# RGB_Matrix.net
KiCad netlist of a schematic drawn in Altium Designer
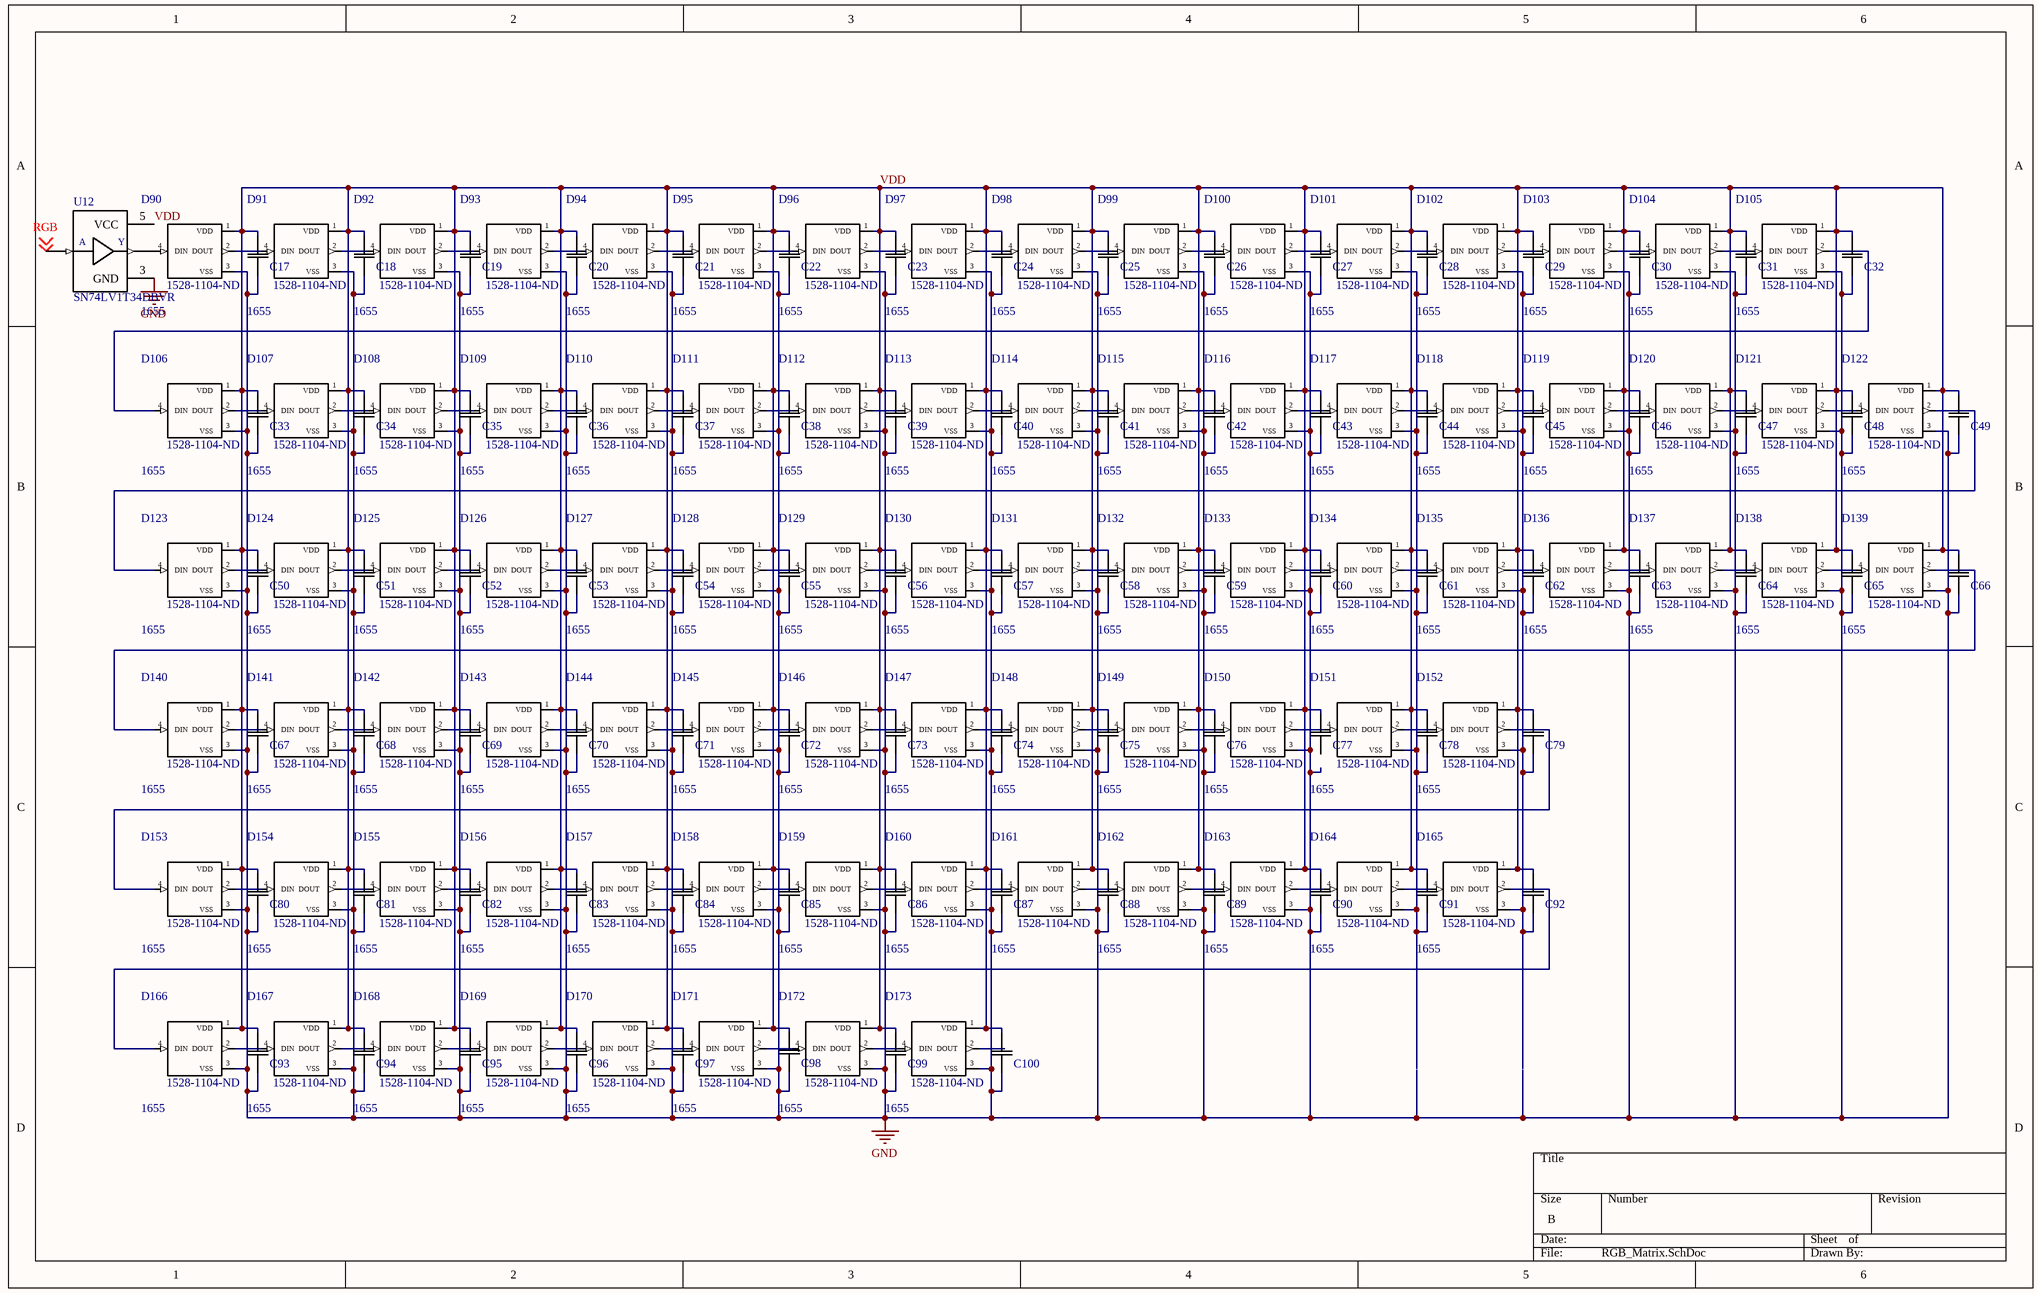
[diagram p0: RGB_Matrix.SchDoc]

(export (version "E")
  (design (tool "Eeschema 10.0.6"))
  (components
    (comp (ref "C17")
      (value "Part Number: RCER71H104K0DBH03A")
      (footprint "RCER71H104K0DBH0")
      (description "No Description Available")
      (fields
        (field (name "MANUFACTURER_PART_NUMBER") "RCER71H104K0DBH03A")
        (field (name "COPYRIGHT") "Copyright (C) 2015 Accelerated Designs. All rights reserved")
      )
      (libsource (lib "RCER71H104K0DBH03A") (part "RCER71H104K0DBH0"))
    )
    (comp (ref "C18")
      (value "Part Number: RCER71H104K0DBH03A")
      (footprint "RCER71H104K0DBH0")
      (description "No Description Available")
      (fields
        (field (name "MANUFACTURER_PART_NUMBER") "RCER71H104K0DBH03A")
        (field (name "COPYRIGHT") "Copyright (C) 2015 Accelerated Designs. All rights reserved")
      )
      (libsource (lib "RCER71H104K0DBH03A") (part "RCER71H104K0DBH0"))
    )
    (comp (ref "C19")
      (value "Part Number: RCER71H104K0DBH03A")
      (footprint "RCER71H104K0DBH0")
      (description "No Description Available")
      (fields
        (field (name "MANUFACTURER_PART_NUMBER") "RCER71H104K0DBH03A")
        (field (name "COPYRIGHT") "Copyright (C) 2015 Accelerated Designs. All rights reserved")
      )
      (libsource (lib "RCER71H104K0DBH03A") (part "RCER71H104K0DBH0"))
    )
    (comp (ref "C20")
      (value "Part Number: RCER71H104K0DBH03A")
      (footprint "RCER71H104K0DBH0")
      (description "No Description Available")
      (fields
        (field (name "MANUFACTURER_PART_NUMBER") "RCER71H104K0DBH03A")
        (field (name "COPYRIGHT") "Copyright (C) 2015 Accelerated Designs. All rights reserved")
      )
      (libsource (lib "RCER71H104K0DBH03A") (part "RCER71H104K0DBH0"))
    )
    (comp (ref "C21")
      (value "Part Number: RCER71H104K0DBH03A")
      (footprint "RCER71H104K0DBH0")
      (description "No Description Available")
      (fields
        (field (name "MANUFACTURER_PART_NUMBER") "RCER71H104K0DBH03A")
        (field (name "COPYRIGHT") "Copyright (C) 2015 Accelerated Designs. All rights reserved")
      )
      (libsource (lib "RCER71H104K0DBH03A") (part "RCER71H104K0DBH0"))
    )
    (comp (ref "C22")
      (value "Part Number: RCER71H104K0DBH03A")
      (footprint "RCER71H104K0DBH0")
      (description "No Description Available")
      (fields
        (field (name "MANUFACTURER_PART_NUMBER") "RCER71H104K0DBH03A")
        (field (name "COPYRIGHT") "Copyright (C) 2015 Accelerated Designs. All rights reserved")
      )
      (libsource (lib "RCER71H104K0DBH03A") (part "RCER71H104K0DBH0"))
    )
    (comp (ref "C23")
      (value "Part Number: RCER71H104K0DBH03A")
      (footprint "RCER71H104K0DBH0")
      (description "No Description Available")
      (fields
        (field (name "MANUFACTURER_PART_NUMBER") "RCER71H104K0DBH03A")
        (field (name "COPYRIGHT") "Copyright (C) 2015 Accelerated Designs. All rights reserved")
      )
      (libsource (lib "RCER71H104K0DBH03A") (part "RCER71H104K0DBH0"))
    )
    (comp (ref "C24")
      (value "Part Number: RCER71H104K0DBH03A")
      (footprint "RCER71H104K0DBH0")
      (description "No Description Available")
      (fields
        (field (name "MANUFACTURER_PART_NUMBER") "RCER71H104K0DBH03A")
        (field (name "COPYRIGHT") "Copyright (C) 2015 Accelerated Designs. All rights reserved")
      )
      (libsource (lib "RCER71H104K0DBH03A") (part "RCER71H104K0DBH0"))
    )
    (comp (ref "C25")
      (value "Part Number: RCER71H104K0DBH03A")
      (footprint "RCER71H104K0DBH0")
      (description "No Description Available")
      (fields
        (field (name "MANUFACTURER_PART_NUMBER") "RCER71H104K0DBH03A")
        (field (name "COPYRIGHT") "Copyright (C) 2015 Accelerated Designs. All rights reserved")
      )
      (libsource (lib "RCER71H104K0DBH03A") (part "RCER71H104K0DBH0"))
    )
    (comp (ref "C26")
      (value "Part Number: RCER71H104K0DBH03A")
      (footprint "RCER71H104K0DBH0")
      (description "No Description Available")
      (fields
        (field (name "MANUFACTURER_PART_NUMBER") "RCER71H104K0DBH03A")
        (field (name "COPYRIGHT") "Copyright (C) 2015 Accelerated Designs. All rights reserved")
      )
      (libsource (lib "RCER71H104K0DBH03A") (part "RCER71H104K0DBH0"))
    )
    (comp (ref "C27")
      (value "Part Number: RCER71H104K0DBH03A")
      (footprint "RCER71H104K0DBH0")
      (description "No Description Available")
      (fields
        (field (name "MANUFACTURER_PART_NUMBER") "RCER71H104K0DBH03A")
        (field (name "COPYRIGHT") "Copyright (C) 2015 Accelerated Designs. All rights reserved")
      )
      (libsource (lib "RCER71H104K0DBH03A") (part "RCER71H104K0DBH0"))
    )
    (comp (ref "C28")
      (value "Part Number: RCER71H104K0DBH03A")
      (footprint "RCER71H104K0DBH0")
      (description "No Description Available")
      (fields
        (field (name "MANUFACTURER_PART_NUMBER") "RCER71H104K0DBH03A")
        (field (name "COPYRIGHT") "Copyright (C) 2015 Accelerated Designs. All rights reserved")
      )
      (libsource (lib "RCER71H104K0DBH03A") (part "RCER71H104K0DBH0"))
    )
    (comp (ref "C29")
      (value "Part Number: RCER71H104K0DBH03A")
      (footprint "RCER71H104K0DBH0")
      (description "No Description Available")
      (fields
        (field (name "MANUFACTURER_PART_NUMBER") "RCER71H104K0DBH03A")
        (field (name "COPYRIGHT") "Copyright (C) 2015 Accelerated Designs. All rights reserved")
      )
      (libsource (lib "RCER71H104K0DBH03A") (part "RCER71H104K0DBH0"))
    )
    (comp (ref "C30")
      (value "Part Number: RCER71H104K0DBH03A")
      (footprint "RCER71H104K0DBH0")
      (description "No Description Available")
      (fields
        (field (name "MANUFACTURER_PART_NUMBER") "RCER71H104K0DBH03A")
        (field (name "COPYRIGHT") "Copyright (C) 2015 Accelerated Designs. All rights reserved")
      )
      (libsource (lib "RCER71H104K0DBH03A") (part "RCER71H104K0DBH0"))
    )
    (comp (ref "C31")
      (value "Part Number: RCER71H104K0DBH03A")
      (footprint "RCER71H104K0DBH0")
      (description "No Description Available")
      (fields
        (field (name "MANUFACTURER_PART_NUMBER") "RCER71H104K0DBH03A")
        (field (name "COPYRIGHT") "Copyright (C) 2015 Accelerated Designs. All rights reserved")
      )
      (libsource (lib "RCER71H104K0DBH03A") (part "RCER71H104K0DBH0"))
    )
    (comp (ref "C32")
      (value "Part Number: RCER71H104K0DBH03A")
      (footprint "RCER71H104K0DBH0")
      (description "No Description Available")
      (fields
        (field (name "MANUFACTURER_PART_NUMBER") "RCER71H104K0DBH03A")
        (field (name "COPYRIGHT") "Copyright (C) 2015 Accelerated Designs. All rights reserved")
      )
      (libsource (lib "RCER71H104K0DBH03A") (part "RCER71H104K0DBH0"))
    )
    (comp (ref "C33")
      (value "Part Number: RCER71H104K0DBH03A")
      (footprint "RCER71H104K0DBH0")
      (description "No Description Available")
      (fields
        (field (name "MANUFACTURER_PART_NUMBER") "RCER71H104K0DBH03A")
        (field (name "COPYRIGHT") "Copyright (C) 2015 Accelerated Designs. All rights reserved")
      )
      (libsource (lib "RCER71H104K0DBH03A") (part "RCER71H104K0DBH0"))
    )
    (comp (ref "C34")
      (value "Part Number: RCER71H104K0DBH03A")
      (footprint "RCER71H104K0DBH0")
      (description "No Description Available")
      (fields
        (field (name "MANUFACTURER_PART_NUMBER") "RCER71H104K0DBH03A")
        (field (name "COPYRIGHT") "Copyright (C) 2015 Accelerated Designs. All rights reserved")
      )
      (libsource (lib "RCER71H104K0DBH03A") (part "RCER71H104K0DBH0"))
    )
    (comp (ref "C35")
      (value "Part Number: RCER71H104K0DBH03A")
      (footprint "RCER71H104K0DBH0")
      (description "No Description Available")
      (fields
        (field (name "MANUFACTURER_PART_NUMBER") "RCER71H104K0DBH03A")
        (field (name "COPYRIGHT") "Copyright (C) 2015 Accelerated Designs. All rights reserved")
      )
      (libsource (lib "RCER71H104K0DBH03A") (part "RCER71H104K0DBH0"))
    )
    (comp (ref "C36")
      (value "Part Number: RCER71H104K0DBH03A")
      (footprint "RCER71H104K0DBH0")
      (description "No Description Available")
      (fields
        (field (name "MANUFACTURER_PART_NUMBER") "RCER71H104K0DBH03A")
        (field (name "COPYRIGHT") "Copyright (C) 2015 Accelerated Designs. All rights reserved")
      )
      (libsource (lib "RCER71H104K0DBH03A") (part "RCER71H104K0DBH0"))
    )
    (comp (ref "C37")
      (value "Part Number: RCER71H104K0DBH03A")
      (footprint "RCER71H104K0DBH0")
      (description "No Description Available")
      (fields
        (field (name "MANUFACTURER_PART_NUMBER") "RCER71H104K0DBH03A")
        (field (name "COPYRIGHT") "Copyright (C) 2015 Accelerated Designs. All rights reserved")
      )
      (libsource (lib "RCER71H104K0DBH03A") (part "RCER71H104K0DBH0"))
    )
    (comp (ref "C38")
      (value "Part Number: RCER71H104K0DBH03A")
      (footprint "RCER71H104K0DBH0")
      (description "No Description Available")
      (fields
        (field (name "MANUFACTURER_PART_NUMBER") "RCER71H104K0DBH03A")
        (field (name "COPYRIGHT") "Copyright (C) 2015 Accelerated Designs. All rights reserved")
      )
      (libsource (lib "RCER71H104K0DBH03A") (part "RCER71H104K0DBH0"))
    )
    (comp (ref "C39")
      (value "Part Number: RCER71H104K0DBH03A")
      (footprint "RCER71H104K0DBH0")
      (description "No Description Available")
      (fields
        (field (name "MANUFACTURER_PART_NUMBER") "RCER71H104K0DBH03A")
        (field (name "COPYRIGHT") "Copyright (C) 2015 Accelerated Designs. All rights reserved")
      )
      (libsource (lib "RCER71H104K0DBH03A") (part "RCER71H104K0DBH0"))
    )
    (comp (ref "C40")
      (value "Part Number: RCER71H104K0DBH03A")
      (footprint "RCER71H104K0DBH0")
      (description "No Description Available")
      (fields
        (field (name "MANUFACTURER_PART_NUMBER") "RCER71H104K0DBH03A")
        (field (name "COPYRIGHT") "Copyright (C) 2015 Accelerated Designs. All rights reserved")
      )
      (libsource (lib "RCER71H104K0DBH03A") (part "RCER71H104K0DBH0"))
    )
    (comp (ref "C41")
      (value "Part Number: RCER71H104K0DBH03A")
      (footprint "RCER71H104K0DBH0")
      (description "No Description Available")
      (fields
        (field (name "MANUFACTURER_PART_NUMBER") "RCER71H104K0DBH03A")
        (field (name "COPYRIGHT") "Copyright (C) 2015 Accelerated Designs. All rights reserved")
      )
      (libsource (lib "RCER71H104K0DBH03A") (part "RCER71H104K0DBH0"))
    )
    (comp (ref "C42")
      (value "Part Number: RCER71H104K0DBH03A")
      (footprint "RCER71H104K0DBH0")
      (description "No Description Available")
      (fields
        (field (name "MANUFACTURER_PART_NUMBER") "RCER71H104K0DBH03A")
        (field (name "COPYRIGHT") "Copyright (C) 2015 Accelerated Designs. All rights reserved")
      )
      (libsource (lib "RCER71H104K0DBH03A") (part "RCER71H104K0DBH0"))
    )
    (comp (ref "C43")
      (value "Part Number: RCER71H104K0DBH03A")
      (footprint "RCER71H104K0DBH0")
      (description "No Description Available")
      (fields
        (field (name "MANUFACTURER_PART_NUMBER") "RCER71H104K0DBH03A")
        (field (name "COPYRIGHT") "Copyright (C) 2015 Accelerated Designs. All rights reserved")
      )
      (libsource (lib "RCER71H104K0DBH03A") (part "RCER71H104K0DBH0"))
    )
    (comp (ref "C44")
      (value "Part Number: RCER71H104K0DBH03A")
      (footprint "RCER71H104K0DBH0")
      (description "No Description Available")
      (fields
        (field (name "MANUFACTURER_PART_NUMBER") "RCER71H104K0DBH03A")
        (field (name "COPYRIGHT") "Copyright (C) 2015 Accelerated Designs. All rights reserved")
      )
      (libsource (lib "RCER71H104K0DBH03A") (part "RCER71H104K0DBH0"))
    )
    (comp (ref "C45")
      (value "Part Number: RCER71H104K0DBH03A")
      (footprint "RCER71H104K0DBH0")
      (description "No Description Available")
      (fields
        (field (name "MANUFACTURER_PART_NUMBER") "RCER71H104K0DBH03A")
        (field (name "COPYRIGHT") "Copyright (C) 2015 Accelerated Designs. All rights reserved")
      )
      (libsource (lib "RCER71H104K0DBH03A") (part "RCER71H104K0DBH0"))
    )
    (comp (ref "C46")
      (value "Part Number: RCER71H104K0DBH03A")
      (footprint "RCER71H104K0DBH0")
      (description "No Description Available")
      (fields
        (field (name "MANUFACTURER_PART_NUMBER") "RCER71H104K0DBH03A")
        (field (name "COPYRIGHT") "Copyright (C) 2015 Accelerated Designs. All rights reserved")
      )
      (libsource (lib "RCER71H104K0DBH03A") (part "RCER71H104K0DBH0"))
    )
    (comp (ref "C47")
      (value "Part Number: RCER71H104K0DBH03A")
      (footprint "RCER71H104K0DBH0")
      (description "No Description Available")
      (fields
        (field (name "MANUFACTURER_PART_NUMBER") "RCER71H104K0DBH03A")
        (field (name "COPYRIGHT") "Copyright (C) 2015 Accelerated Designs. All rights reserved")
      )
      (libsource (lib "RCER71H104K0DBH03A") (part "RCER71H104K0DBH0"))
    )
    (comp (ref "C48")
      (value "Part Number: RCER71H104K0DBH03A")
      (footprint "RCER71H104K0DBH0")
      (description "No Description Available")
      (fields
        (field (name "MANUFACTURER_PART_NUMBER") "RCER71H104K0DBH03A")
        (field (name "COPYRIGHT") "Copyright (C) 2015 Accelerated Designs. All rights reserved")
      )
      (libsource (lib "RCER71H104K0DBH03A") (part "RCER71H104K0DBH0"))
    )
    (comp (ref "C49")
      (value "Part Number: RCER71H104K0DBH03A")
      (footprint "RCER71H104K0DBH0")
      (description "No Description Available")
      (fields
        (field (name "MANUFACTURER_PART_NUMBER") "RCER71H104K0DBH03A")
        (field (name "COPYRIGHT") "Copyright (C) 2015 Accelerated Designs. All rights reserved")
      )
      (libsource (lib "RCER71H104K0DBH03A") (part "RCER71H104K0DBH0"))
    )
    (comp (ref "C50")
      (value "Part Number: RCER71H104K0DBH03A")
      (footprint "RCER71H104K0DBH0")
      (description "No Description Available")
      (fields
        (field (name "MANUFACTURER_PART_NUMBER") "RCER71H104K0DBH03A")
        (field (name "COPYRIGHT") "Copyright (C) 2015 Accelerated Designs. All rights reserved")
      )
      (libsource (lib "RCER71H104K0DBH03A") (part "RCER71H104K0DBH0"))
    )
    (comp (ref "C51")
      (value "Part Number: RCER71H104K0DBH03A")
      (footprint "RCER71H104K0DBH0")
      (description "No Description Available")
      (fields
        (field (name "MANUFACTURER_PART_NUMBER") "RCER71H104K0DBH03A")
        (field (name "COPYRIGHT") "Copyright (C) 2015 Accelerated Designs. All rights reserved")
      )
      (libsource (lib "RCER71H104K0DBH03A") (part "RCER71H104K0DBH0"))
    )
    (comp (ref "C52")
      (value "Part Number: RCER71H104K0DBH03A")
      (footprint "RCER71H104K0DBH0")
      (description "No Description Available")
      (fields
        (field (name "MANUFACTURER_PART_NUMBER") "RCER71H104K0DBH03A")
        (field (name "COPYRIGHT") "Copyright (C) 2015 Accelerated Designs. All rights reserved")
      )
      (libsource (lib "RCER71H104K0DBH03A") (part "RCER71H104K0DBH0"))
    )
    (comp (ref "C53")
      (value "Part Number: RCER71H104K0DBH03A")
      (footprint "RCER71H104K0DBH0")
      (description "No Description Available")
      (fields
        (field (name "MANUFACTURER_PART_NUMBER") "RCER71H104K0DBH03A")
        (field (name "COPYRIGHT") "Copyright (C) 2015 Accelerated Designs. All rights reserved")
      )
      (libsource (lib "RCER71H104K0DBH03A") (part "RCER71H104K0DBH0"))
    )
    (comp (ref "C54")
      (value "Part Number: RCER71H104K0DBH03A")
      (footprint "RCER71H104K0DBH0")
      (description "No Description Available")
      (fields
        (field (name "MANUFACTURER_PART_NUMBER") "RCER71H104K0DBH03A")
        (field (name "COPYRIGHT") "Copyright (C) 2015 Accelerated Designs. All rights reserved")
      )
      (libsource (lib "RCER71H104K0DBH03A") (part "RCER71H104K0DBH0"))
    )
    (comp (ref "C55")
      (value "Part Number: RCER71H104K0DBH03A")
      (footprint "RCER71H104K0DBH0")
      (description "No Description Available")
      (fields
        (field (name "MANUFACTURER_PART_NUMBER") "RCER71H104K0DBH03A")
        (field (name "COPYRIGHT") "Copyright (C) 2015 Accelerated Designs. All rights reserved")
      )
      (libsource (lib "RCER71H104K0DBH03A") (part "RCER71H104K0DBH0"))
    )
    (comp (ref "C56")
      (value "Part Number: RCER71H104K0DBH03A")
      (footprint "RCER71H104K0DBH0")
      (description "No Description Available")
      (fields
        (field (name "MANUFACTURER_PART_NUMBER") "RCER71H104K0DBH03A")
        (field (name "COPYRIGHT") "Copyright (C) 2015 Accelerated Designs. All rights reserved")
      )
      (libsource (lib "RCER71H104K0DBH03A") (part "RCER71H104K0DBH0"))
    )
    (comp (ref "C57")
      (value "Part Number: RCER71H104K0DBH03A")
      (footprint "RCER71H104K0DBH0")
      (description "No Description Available")
      (fields
        (field (name "MANUFACTURER_PART_NUMBER") "RCER71H104K0DBH03A")
        (field (name "COPYRIGHT") "Copyright (C) 2015 Accelerated Designs. All rights reserved")
      )
      (libsource (lib "RCER71H104K0DBH03A") (part "RCER71H104K0DBH0"))
    )
    (comp (ref "C58")
      (value "Part Number: RCER71H104K0DBH03A")
      (footprint "RCER71H104K0DBH0")
      (description "No Description Available")
      (fields
        (field (name "MANUFACTURER_PART_NUMBER") "RCER71H104K0DBH03A")
        (field (name "COPYRIGHT") "Copyright (C) 2015 Accelerated Designs. All rights reserved")
      )
      (libsource (lib "RCER71H104K0DBH03A") (part "RCER71H104K0DBH0"))
    )
    (comp (ref "C59")
      (value "Part Number: RCER71H104K0DBH03A")
      (footprint "RCER71H104K0DBH0")
      (description "No Description Available")
      (fields
        (field (name "MANUFACTURER_PART_NUMBER") "RCER71H104K0DBH03A")
        (field (name "COPYRIGHT") "Copyright (C) 2015 Accelerated Designs. All rights reserved")
      )
      (libsource (lib "RCER71H104K0DBH03A") (part "RCER71H104K0DBH0"))
    )
    (comp (ref "C60")
      (value "Part Number: RCER71H104K0DBH03A")
      (footprint "RCER71H104K0DBH0")
      (description "No Description Available")
      (fields
        (field (name "MANUFACTURER_PART_NUMBER") "RCER71H104K0DBH03A")
        (field (name "COPYRIGHT") "Copyright (C) 2015 Accelerated Designs. All rights reserved")
      )
      (libsource (lib "RCER71H104K0DBH03A") (part "RCER71H104K0DBH0"))
    )
    (comp (ref "C61")
      (value "Part Number: RCER71H104K0DBH03A")
      (footprint "RCER71H104K0DBH0")
      (description "No Description Available")
      (fields
        (field (name "MANUFACTURER_PART_NUMBER") "RCER71H104K0DBH03A")
        (field (name "COPYRIGHT") "Copyright (C) 2015 Accelerated Designs. All rights reserved")
      )
      (libsource (lib "RCER71H104K0DBH03A") (part "RCER71H104K0DBH0"))
    )
    (comp (ref "C62")
      (value "Part Number: RCER71H104K0DBH03A")
      (footprint "RCER71H104K0DBH0")
      (description "No Description Available")
      (fields
        (field (name "MANUFACTURER_PART_NUMBER") "RCER71H104K0DBH03A")
        (field (name "COPYRIGHT") "Copyright (C) 2015 Accelerated Designs. All rights reserved")
      )
      (libsource (lib "RCER71H104K0DBH03A") (part "RCER71H104K0DBH0"))
    )
    (comp (ref "C63")
      (value "Part Number: RCER71H104K0DBH03A")
      (footprint "RCER71H104K0DBH0")
      (description "No Description Available")
      (fields
        (field (name "MANUFACTURER_PART_NUMBER") "RCER71H104K0DBH03A")
        (field (name "COPYRIGHT") "Copyright (C) 2015 Accelerated Designs. All rights reserved")
      )
      (libsource (lib "RCER71H104K0DBH03A") (part "RCER71H104K0DBH0"))
    )
    (comp (ref "C64")
      (value "Part Number: RCER71H104K0DBH03A")
      (footprint "RCER71H104K0DBH0")
      (description "No Description Available")
      (fields
        (field (name "MANUFACTURER_PART_NUMBER") "RCER71H104K0DBH03A")
        (field (name "COPYRIGHT") "Copyright (C) 2015 Accelerated Designs. All rights reserved")
      )
      (libsource (lib "RCER71H104K0DBH03A") (part "RCER71H104K0DBH0"))
    )
    (comp (ref "C65")
      (value "Part Number: RCER71H104K0DBH03A")
      (footprint "RCER71H104K0DBH0")
      (description "No Description Available")
      (fields
        (field (name "MANUFACTURER_PART_NUMBER") "RCER71H104K0DBH03A")
        (field (name "COPYRIGHT") "Copyright (C) 2015 Accelerated Designs. All rights reserved")
      )
      (libsource (lib "RCER71H104K0DBH03A") (part "RCER71H104K0DBH0"))
    )
    (comp (ref "C66")
      (value "Part Number: RCER71H104K0DBH03A")
      (footprint "RCER71H104K0DBH0")
      (description "No Description Available")
      (fields
        (field (name "MANUFACTURER_PART_NUMBER") "RCER71H104K0DBH03A")
        (field (name "COPYRIGHT") "Copyright (C) 2015 Accelerated Designs. All rights reserved")
      )
      (libsource (lib "RCER71H104K0DBH03A") (part "RCER71H104K0DBH0"))
    )
    (comp (ref "C67")
      (value "Part Number: RCER71H104K0DBH03A")
      (footprint "RCER71H104K0DBH0")
      (description "No Description Available")
      (fields
        (field (name "MANUFACTURER_PART_NUMBER") "RCER71H104K0DBH03A")
        (field (name "COPYRIGHT") "Copyright (C) 2015 Accelerated Designs. All rights reserved")
      )
      (libsource (lib "RCER71H104K0DBH03A") (part "RCER71H104K0DBH0"))
    )
    (comp (ref "C68")
      (value "Part Number: RCER71H104K0DBH03A")
      (footprint "RCER71H104K0DBH0")
      (description "No Description Available")
      (fields
        (field (name "MANUFACTURER_PART_NUMBER") "RCER71H104K0DBH03A")
        (field (name "COPYRIGHT") "Copyright (C) 2015 Accelerated Designs. All rights reserved")
      )
      (libsource (lib "RCER71H104K0DBH03A") (part "RCER71H104K0DBH0"))
    )
    (comp (ref "C69")
      (value "Part Number: RCER71H104K0DBH03A")
      (footprint "RCER71H104K0DBH0")
      (description "No Description Available")
      (fields
        (field (name "MANUFACTURER_PART_NUMBER") "RCER71H104K0DBH03A")
        (field (name "COPYRIGHT") "Copyright (C) 2015 Accelerated Designs. All rights reserved")
      )
      (libsource (lib "RCER71H104K0DBH03A") (part "RCER71H104K0DBH0"))
    )
    (comp (ref "C70")
      (value "Part Number: RCER71H104K0DBH03A")
      (footprint "RCER71H104K0DBH0")
      (description "No Description Available")
      (fields
        (field (name "MANUFACTURER_PART_NUMBER") "RCER71H104K0DBH03A")
        (field (name "COPYRIGHT") "Copyright (C) 2015 Accelerated Designs. All rights reserved")
      )
      (libsource (lib "RCER71H104K0DBH03A") (part "RCER71H104K0DBH0"))
    )
    (comp (ref "C71")
      (value "Part Number: RCER71H104K0DBH03A")
      (footprint "RCER71H104K0DBH0")
      (description "No Description Available")
      (fields
        (field (name "MANUFACTURER_PART_NUMBER") "RCER71H104K0DBH03A")
        (field (name "COPYRIGHT") "Copyright (C) 2015 Accelerated Designs. All rights reserved")
      )
      (libsource (lib "RCER71H104K0DBH03A") (part "RCER71H104K0DBH0"))
    )
    (comp (ref "C72")
      (value "Part Number: RCER71H104K0DBH03A")
      (footprint "RCER71H104K0DBH0")
      (description "No Description Available")
      (fields
        (field (name "MANUFACTURER_PART_NUMBER") "RCER71H104K0DBH03A")
        (field (name "COPYRIGHT") "Copyright (C) 2015 Accelerated Designs. All rights reserved")
      )
      (libsource (lib "RCER71H104K0DBH03A") (part "RCER71H104K0DBH0"))
    )
    (comp (ref "C73")
      (value "Part Number: RCER71H104K0DBH03A")
      (footprint "RCER71H104K0DBH0")
      (description "No Description Available")
      (fields
        (field (name "MANUFACTURER_PART_NUMBER") "RCER71H104K0DBH03A")
        (field (name "COPYRIGHT") "Copyright (C) 2015 Accelerated Designs. All rights reserved")
      )
      (libsource (lib "RCER71H104K0DBH03A") (part "RCER71H104K0DBH0"))
    )
    (comp (ref "C74")
      (value "Part Number: RCER71H104K0DBH03A")
      (footprint "RCER71H104K0DBH0")
      (description "No Description Available")
      (fields
        (field (name "MANUFACTURER_PART_NUMBER") "RCER71H104K0DBH03A")
        (field (name "COPYRIGHT") "Copyright (C) 2015 Accelerated Designs. All rights reserved")
      )
      (libsource (lib "RCER71H104K0DBH03A") (part "RCER71H104K0DBH0"))
    )
    (comp (ref "C75")
      (value "Part Number: RCER71H104K0DBH03A")
      (footprint "RCER71H104K0DBH0")
      (description "No Description Available")
      (fields
        (field (name "MANUFACTURER_PART_NUMBER") "RCER71H104K0DBH03A")
        (field (name "COPYRIGHT") "Copyright (C) 2015 Accelerated Designs. All rights reserved")
      )
      (libsource (lib "RCER71H104K0DBH03A") (part "RCER71H104K0DBH0"))
    )
    (comp (ref "C76")
      (value "Part Number: RCER71H104K0DBH03A")
      (footprint "RCER71H104K0DBH0")
      (description "No Description Available")
      (fields
        (field (name "MANUFACTURER_PART_NUMBER") "RCER71H104K0DBH03A")
        (field (name "COPYRIGHT") "Copyright (C) 2015 Accelerated Designs. All rights reserved")
      )
      (libsource (lib "RCER71H104K0DBH03A") (part "RCER71H104K0DBH0"))
    )
    (comp (ref "C77")
      (value "Part Number: RCER71H104K0DBH03A")
      (footprint "RCER71H104K0DBH0")
      (description "No Description Available")
      (fields
        (field (name "MANUFACTURER_PART_NUMBER") "RCER71H104K0DBH03A")
        (field (name "COPYRIGHT") "Copyright (C) 2015 Accelerated Designs. All rights reserved")
      )
      (libsource (lib "RCER71H104K0DBH03A") (part "RCER71H104K0DBH0"))
    )
    (comp (ref "C78")
      (value "Part Number: RCER71H104K0DBH03A")
      (footprint "RCER71H104K0DBH0")
      (description "No Description Available")
      (fields
        (field (name "MANUFACTURER_PART_NUMBER") "RCER71H104K0DBH03A")
        (field (name "COPYRIGHT") "Copyright (C) 2015 Accelerated Designs. All rights reserved")
      )
      (libsource (lib "RCER71H104K0DBH03A") (part "RCER71H104K0DBH0"))
    )
    (comp (ref "C79")
      (value "Part Number: RCER71H104K0DBH03A")
      (footprint "RCER71H104K0DBH0")
      (description "No Description Available")
      (fields
        (field (name "MANUFACTURER_PART_NUMBER") "RCER71H104K0DBH03A")
        (field (name "COPYRIGHT") "Copyright (C) 2015 Accelerated Designs. All rights reserved")
      )
      (libsource (lib "RCER71H104K0DBH03A") (part "RCER71H104K0DBH0"))
    )
    (comp (ref "C80")
      (value "Part Number: RCER71H104K0DBH03A")
      (footprint "RCER71H104K0DBH0")
      (description "No Description Available")
      (fields
        (field (name "MANUFACTURER_PART_NUMBER") "RCER71H104K0DBH03A")
        (field (name "COPYRIGHT") "Copyright (C) 2015 Accelerated Designs. All rights reserved")
      )
      (libsource (lib "RCER71H104K0DBH03A") (part "RCER71H104K0DBH0"))
    )
    (comp (ref "C81")
      (value "Part Number: RCER71H104K0DBH03A")
      (footprint "RCER71H104K0DBH0")
      (description "No Description Available")
      (fields
        (field (name "MANUFACTURER_PART_NUMBER") "RCER71H104K0DBH03A")
        (field (name "COPYRIGHT") "Copyright (C) 2015 Accelerated Designs. All rights reserved")
      )
      (libsource (lib "RCER71H104K0DBH03A") (part "RCER71H104K0DBH0"))
    )
    (comp (ref "C82")
      (value "Part Number: RCER71H104K0DBH03A")
      (footprint "RCER71H104K0DBH0")
      (description "No Description Available")
      (fields
        (field (name "MANUFACTURER_PART_NUMBER") "RCER71H104K0DBH03A")
        (field (name "COPYRIGHT") "Copyright (C) 2015 Accelerated Designs. All rights reserved")
      )
      (libsource (lib "RCER71H104K0DBH03A") (part "RCER71H104K0DBH0"))
    )
    (comp (ref "C83")
      (value "Part Number: RCER71H104K0DBH03A")
      (footprint "RCER71H104K0DBH0")
      (description "No Description Available")
      (fields
        (field (name "MANUFACTURER_PART_NUMBER") "RCER71H104K0DBH03A")
        (field (name "COPYRIGHT") "Copyright (C) 2015 Accelerated Designs. All rights reserved")
      )
      (libsource (lib "RCER71H104K0DBH03A") (part "RCER71H104K0DBH0"))
    )
    (comp (ref "C84")
      (value "Part Number: RCER71H104K0DBH03A")
      (footprint "RCER71H104K0DBH0")
      (description "No Description Available")
      (fields
        (field (name "MANUFACTURER_PART_NUMBER") "RCER71H104K0DBH03A")
        (field (name "COPYRIGHT") "Copyright (C) 2015 Accelerated Designs. All rights reserved")
      )
      (libsource (lib "RCER71H104K0DBH03A") (part "RCER71H104K0DBH0"))
    )
    (comp (ref "C85")
      (value "Part Number: RCER71H104K0DBH03A")
      (footprint "RCER71H104K0DBH0")
      (description "No Description Available")
      (fields
        (field (name "MANUFACTURER_PART_NUMBER") "RCER71H104K0DBH03A")
        (field (name "COPYRIGHT") "Copyright (C) 2015 Accelerated Designs. All rights reserved")
      )
      (libsource (lib "RCER71H104K0DBH03A") (part "RCER71H104K0DBH0"))
    )
    (comp (ref "C86")
      (value "Part Number: RCER71H104K0DBH03A")
      (footprint "RCER71H104K0DBH0")
      (description "No Description Available")
      (fields
        (field (name "MANUFACTURER_PART_NUMBER") "RCER71H104K0DBH03A")
        (field (name "COPYRIGHT") "Copyright (C) 2015 Accelerated Designs. All rights reserved")
      )
      (libsource (lib "RCER71H104K0DBH03A") (part "RCER71H104K0DBH0"))
    )
    (comp (ref "C87")
      (value "Part Number: RCER71H104K0DBH03A")
      (footprint "RCER71H104K0DBH0")
      (description "No Description Available")
      (fields
        (field (name "MANUFACTURER_PART_NUMBER") "RCER71H104K0DBH03A")
        (field (name "COPYRIGHT") "Copyright (C) 2015 Accelerated Designs. All rights reserved")
      )
      (libsource (lib "RCER71H104K0DBH03A") (part "RCER71H104K0DBH0"))
    )
    (comp (ref "C88")
      (value "Part Number: RCER71H104K0DBH03A")
      (footprint "RCER71H104K0DBH0")
      (description "No Description Available")
      (fields
        (field (name "MANUFACTURER_PART_NUMBER") "RCER71H104K0DBH03A")
        (field (name "COPYRIGHT") "Copyright (C) 2015 Accelerated Designs. All rights reserved")
      )
      (libsource (lib "RCER71H104K0DBH03A") (part "RCER71H104K0DBH0"))
    )
    (comp (ref "C89")
      (value "Part Number: RCER71H104K0DBH03A")
      (footprint "RCER71H104K0DBH0")
      (description "No Description Available")
      (fields
        (field (name "MANUFACTURER_PART_NUMBER") "RCER71H104K0DBH03A")
        (field (name "COPYRIGHT") "Copyright (C) 2015 Accelerated Designs. All rights reserved")
      )
      (libsource (lib "RCER71H104K0DBH03A") (part "RCER71H104K0DBH0"))
    )
    (comp (ref "C90")
      (value "Part Number: RCER71H104K0DBH03A")
      (footprint "RCER71H104K0DBH0")
      (description "No Description Available")
      (fields
        (field (name "MANUFACTURER_PART_NUMBER") "RCER71H104K0DBH03A")
        (field (name "COPYRIGHT") "Copyright (C) 2015 Accelerated Designs. All rights reserved")
      )
      (libsource (lib "RCER71H104K0DBH03A") (part "RCER71H104K0DBH0"))
    )
    (comp (ref "C91")
      (value "Part Number: RCER71H104K0DBH03A")
      (footprint "RCER71H104K0DBH0")
      (description "No Description Available")
      (fields
        (field (name "MANUFACTURER_PART_NUMBER") "RCER71H104K0DBH03A")
        (field (name "COPYRIGHT") "Copyright (C) 2015 Accelerated Designs. All rights reserved")
      )
      (libsource (lib "RCER71H104K0DBH03A") (part "RCER71H104K0DBH0"))
    )
    (comp (ref "C92")
      (value "Part Number: RCER71H104K0DBH03A")
      (footprint "RCER71H104K0DBH0")
      (description "No Description Available")
      (fields
        (field (name "MANUFACTURER_PART_NUMBER") "RCER71H104K0DBH03A")
        (field (name "COPYRIGHT") "Copyright (C) 2015 Accelerated Designs. All rights reserved")
      )
      (libsource (lib "RCER71H104K0DBH03A") (part "RCER71H104K0DBH0"))
    )
    (comp (ref "C93")
      (value "Part Number: RCER71H104K0DBH03A")
      (footprint "RCER71H104K0DBH0")
      (description "No Description Available")
      (fields
        (field (name "MANUFACTURER_PART_NUMBER") "RCER71H104K0DBH03A")
        (field (name "COPYRIGHT") "Copyright (C) 2015 Accelerated Designs. All rights reserved")
      )
      (libsource (lib "RCER71H104K0DBH03A") (part "RCER71H104K0DBH0"))
    )
    (comp (ref "C94")
      (value "Part Number: RCER71H104K0DBH03A")
      (footprint "RCER71H104K0DBH0")
      (description "No Description Available")
      (fields
        (field (name "MANUFACTURER_PART_NUMBER") "RCER71H104K0DBH03A")
        (field (name "COPYRIGHT") "Copyright (C) 2015 Accelerated Designs. All rights reserved")
      )
      (libsource (lib "RCER71H104K0DBH03A") (part "RCER71H104K0DBH0"))
    )
    (comp (ref "C95")
      (value "Part Number: RCER71H104K0DBH03A")
      (footprint "RCER71H104K0DBH0")
      (description "No Description Available")
      (fields
        (field (name "MANUFACTURER_PART_NUMBER") "RCER71H104K0DBH03A")
        (field (name "COPYRIGHT") "Copyright (C) 2015 Accelerated Designs. All rights reserved")
      )
      (libsource (lib "RCER71H104K0DBH03A") (part "RCER71H104K0DBH0"))
    )
    (comp (ref "C96")
      (value "Part Number: RCER71H104K0DBH03A")
      (footprint "RCER71H104K0DBH0")
      (description "No Description Available")
      (fields
        (field (name "MANUFACTURER_PART_NUMBER") "RCER71H104K0DBH03A")
        (field (name "COPYRIGHT") "Copyright (C) 2015 Accelerated Designs. All rights reserved")
      )
      (libsource (lib "RCER71H104K0DBH03A") (part "RCER71H104K0DBH0"))
    )
    (comp (ref "C97")
      (value "Part Number: RCER71H104K0DBH03A")
      (footprint "RCER71H104K0DBH0")
      (description "No Description Available")
      (fields
        (field (name "MANUFACTURER_PART_NUMBER") "RCER71H104K0DBH03A")
        (field (name "COPYRIGHT") "Copyright (C) 2015 Accelerated Designs. All rights reserved")
      )
      (libsource (lib "RCER71H104K0DBH03A") (part "RCER71H104K0DBH0"))
    )
    (comp (ref "C98")
      (value "Part Number: RCER71H104K0DBH03A")
      (footprint "RCER71H104K0DBH0")
      (description "No Description Available")
      (fields
        (field (name "MANUFACTURER_PART_NUMBER") "RCER71H104K0DBH03A")
        (field (name "COPYRIGHT") "Copyright (C) 2015 Accelerated Designs. All rights reserved")
      )
      (libsource (lib "RCER71H104K0DBH03A") (part "RCER71H104K0DBH0"))
    )
    (comp (ref "C99")
      (value "Part Number: RCER71H104K0DBH03A")
      (footprint "RCER71H104K0DBH0")
      (description "No Description Available")
      (fields
        (field (name "MANUFACTURER_PART_NUMBER") "RCER71H104K0DBH03A")
        (field (name "COPYRIGHT") "Copyright (C) 2015 Accelerated Designs. All rights reserved")
      )
      (libsource (lib "RCER71H104K0DBH03A") (part "RCER71H104K0DBH0"))
    )
    (comp (ref "C100")
      (value "Part Number: RCER71H104K0DBH03A")
      (footprint "RCER71H104K0DBH0")
      (description "No Description Available")
      (fields
        (field (name "MANUFACTURER_PART_NUMBER") "RCER71H104K0DBH03A")
        (field (name "COPYRIGHT") "Copyright (C) 2015 Accelerated Designs. All rights reserved")
      )
      (libsource (lib "RCER71H104K0DBH03A") (part "RCER71H104K0DBH0"))
    )
    (comp (ref "D90")
      (value "1655")
      (footprint "WS2182b_Underside")
      (description "Ws2812b 5050 Rgb Led With Integrated Driver Chip Pack Of 10")
      (fields (field (name "MF") "Adafruit") (field (name "SUPPLIER PART NUMBER 1") "1528-1104-ND"))
      (libsource (lib "1655") (part "1655"))
    )
    (comp (ref "D91")
      (value "1655")
      (footprint "WS2182b_Underside")
      (description "Ws2812b 5050 Rgb Led With Integrated Driver Chip Pack Of 10")
      (fields (field (name "MF") "Adafruit") (field (name "SUPPLIER PART NUMBER 1") "1528-1104-ND"))
      (libsource (lib "1655") (part "1655"))
    )
    (comp (ref "D92")
      (value "1655")
      (footprint "WS2182b_Underside")
      (description "Ws2812b 5050 Rgb Led With Integrated Driver Chip Pack Of 10")
      (fields (field (name "MF") "Adafruit") (field (name "SUPPLIER PART NUMBER 1") "1528-1104-ND"))
      (libsource (lib "1655") (part "1655"))
    )
    (comp (ref "D93")
      (value "1655")
      (footprint "WS2182b_Underside")
      (description "Ws2812b 5050 Rgb Led With Integrated Driver Chip Pack Of 10")
      (fields (field (name "MF") "Adafruit") (field (name "SUPPLIER PART NUMBER 1") "1528-1104-ND"))
      (libsource (lib "1655") (part "1655"))
    )
    (comp (ref "D94")
      (value "1655")
      (footprint "WS2182b_Underside")
      (description "Ws2812b 5050 Rgb Led With Integrated Driver Chip Pack Of 10")
      (fields (field (name "MF") "Adafruit") (field (name "SUPPLIER PART NUMBER 1") "1528-1104-ND"))
      (libsource (lib "1655") (part "1655"))
    )
    (comp (ref "D95")
      (value "1655")
      (footprint "WS2182b_Underside")
      (description "Ws2812b 5050 Rgb Led With Integrated Driver Chip Pack Of 10")
      (fields (field (name "MF") "Adafruit") (field (name "SUPPLIER PART NUMBER 1") "1528-1104-ND"))
      (libsource (lib "1655") (part "1655"))
    )
    (comp (ref "D96")
      (value "1655")
      (footprint "WS2182b_Underside")
      (description "Ws2812b 5050 Rgb Led With Integrated Driver Chip Pack Of 10")
      (fields (field (name "MF") "Adafruit") (field (name "SUPPLIER PART NUMBER 1") "1528-1104-ND"))
      (libsource (lib "1655") (part "1655"))
    )
    (comp (ref "D97")
      (value "1655")
      (footprint "WS2182b_Underside")
      (description "Ws2812b 5050 Rgb Led With Integrated Driver Chip Pack Of 10")
      (fields (field (name "MF") "Adafruit") (field (name "SUPPLIER PART NUMBER 1") "1528-1104-ND"))
      (libsource (lib "1655") (part "1655"))
    )
    (comp (ref "D98")
      (value "1655")
      (footprint "WS2182b_Underside")
      (description "Ws2812b 5050 Rgb Led With Integrated Driver Chip Pack Of 10")
      (fields (field (name "MF") "Adafruit") (field (name "SUPPLIER PART NUMBER 1") "1528-1104-ND"))
      (libsource (lib "1655") (part "1655"))
    )
    (comp (ref "D99")
      (value "1655")
      (footprint "WS2182b_Underside")
      (description "Ws2812b 5050 Rgb Led With Integrated Driver Chip Pack Of 10")
      (fields (field (name "MF") "Adafruit") (field (name "SUPPLIER PART NUMBER 1") "1528-1104-ND"))
      (libsource (lib "1655") (part "1655"))
    )
    (comp (ref "D100")
      (value "1655")
      (footprint "WS2182b_Underside")
      (description "Ws2812b 5050 Rgb Led With Integrated Driver Chip Pack Of 10")
      (fields (field (name "MF") "Adafruit") (field (name "SUPPLIER PART NUMBER 1") "1528-1104-ND"))
      (libsource (lib "1655") (part "1655"))
    )
    (comp (ref "D101")
      (value "1655")
      (footprint "WS2182b_Underside")
      (description "Ws2812b 5050 Rgb Led With Integrated Driver Chip Pack Of 10")
      (fields (field (name "MF") "Adafruit") (field (name "SUPPLIER PART NUMBER 1") "1528-1104-ND"))
      (libsource (lib "1655") (part "1655"))
    )
    (comp (ref "D102")
      (value "1655")
      (footprint "WS2182b_Underside")
      (description "Ws2812b 5050 Rgb Led With Integrated Driver Chip Pack Of 10")
      (fields (field (name "MF") "Adafruit") (field (name "SUPPLIER PART NUMBER 1") "1528-1104-ND"))
      (libsource (lib "1655") (part "1655"))
    )
    (comp (ref "D103")
      (value "1655")
      (footprint "WS2182b_Underside")
      (description "Ws2812b 5050 Rgb Led With Integrated Driver Chip Pack Of 10")
      (fields (field (name "MF") "Adafruit") (field (name "SUPPLIER PART NUMBER 1") "1528-1104-ND"))
      (libsource (lib "1655") (part "1655"))
    )
    (comp (ref "D104")
      (value "1655")
      (footprint "WS2182b_Underside")
      (description "Ws2812b 5050 Rgb Led With Integrated Driver Chip Pack Of 10")
      (fields (field (name "MF") "Adafruit") (field (name "SUPPLIER PART NUMBER 1") "1528-1104-ND"))
      (libsource (lib "1655") (part "1655"))
    )
    (comp (ref "D105")
      (value "1655")
      (footprint "WS2182b_Underside")
      (description "Ws2812b 5050 Rgb Led With Integrated Driver Chip Pack Of 10")
      (fields (field (name "MF") "Adafruit") (field (name "SUPPLIER PART NUMBER 1") "1528-1104-ND"))
      (libsource (lib "1655") (part "1655"))
    )
    (comp (ref "D106")
      (value "1655")
      (footprint "WS2182b_Underside")
      (description "Ws2812b 5050 Rgb Led With Integrated Driver Chip Pack Of 10")
      (fields (field (name "MF") "Adafruit") (field (name "SUPPLIER PART NUMBER 1") "1528-1104-ND"))
      (libsource (lib "1655") (part "1655"))
    )
    (comp (ref "D107")
      (value "1655")
      (footprint "WS2182b_Underside")
      (description "Ws2812b 5050 Rgb Led With Integrated Driver Chip Pack Of 10")
      (fields (field (name "MF") "Adafruit") (field (name "SUPPLIER PART NUMBER 1") "1528-1104-ND"))
      (libsource (lib "1655") (part "1655"))
    )
    (comp (ref "D108")
      (value "1655")
      (footprint "WS2182b_Underside")
      (description "Ws2812b 5050 Rgb Led With Integrated Driver Chip Pack Of 10")
      (fields (field (name "MF") "Adafruit") (field (name "SUPPLIER PART NUMBER 1") "1528-1104-ND"))
      (libsource (lib "1655") (part "1655"))
    )
    (comp (ref "D109")
      (value "1655")
      (footprint "WS2182b_Underside")
      (description "Ws2812b 5050 Rgb Led With Integrated Driver Chip Pack Of 10")
      (fields (field (name "MF") "Adafruit") (field (name "SUPPLIER PART NUMBER 1") "1528-1104-ND"))
      (libsource (lib "1655") (part "1655"))
    )
    (comp (ref "D110")
      (value "1655")
      (footprint "WS2182b_Underside")
      (description "Ws2812b 5050 Rgb Led With Integrated Driver Chip Pack Of 10")
      (fields (field (name "MF") "Adafruit") (field (name "SUPPLIER PART NUMBER 1") "1528-1104-ND"))
      (libsource (lib "1655") (part "1655"))
    )
    (comp (ref "D111")
      (value "1655")
      (footprint "WS2182b_Underside")
      (description "Ws2812b 5050 Rgb Led With Integrated Driver Chip Pack Of 10")
      (fields (field (name "MF") "Adafruit") (field (name "SUPPLIER PART NUMBER 1") "1528-1104-ND"))
      (libsource (lib "1655") (part "1655"))
    )
    (comp (ref "D112")
      (value "1655")
      (footprint "WS2182b_Underside")
      (description "Ws2812b 5050 Rgb Led With Integrated Driver Chip Pack Of 10")
      (fields (field (name "MF") "Adafruit") (field (name "SUPPLIER PART NUMBER 1") "1528-1104-ND"))
      (libsource (lib "1655") (part "1655"))
    )
    (comp (ref "D113")
      (value "1655")
      (footprint "WS2182b_Underside")
      (description "Ws2812b 5050 Rgb Led With Integrated Driver Chip Pack Of 10")
      (fields (field (name "MF") "Adafruit") (field (name "SUPPLIER PART NUMBER 1") "1528-1104-ND"))
      (libsource (lib "1655") (part "1655"))
    )
    (comp (ref "D114")
      (value "1655")
      (footprint "WS2182b_Underside")
      (description "Ws2812b 5050 Rgb Led With Integrated Driver Chip Pack Of 10")
      (fields (field (name "MF") "Adafruit") (field (name "SUPPLIER PART NUMBER 1") "1528-1104-ND"))
      (libsource (lib "1655") (part "1655"))
    )
    (comp (ref "D115")
      (value "1655")
      (footprint "WS2182b_Underside")
      (description "Ws2812b 5050 Rgb Led With Integrated Driver Chip Pack Of 10")
      (fields (field (name "MF") "Adafruit") (field (name "SUPPLIER PART NUMBER 1") "1528-1104-ND"))
      (libsource (lib "1655") (part "1655"))
    )
    (comp (ref "D116")
      (value "1655")
      (footprint "WS2182b_Underside")
      (description "Ws2812b 5050 Rgb Led With Integrated Driver Chip Pack Of 10")
      (fields (field (name "MF") "Adafruit") (field (name "SUPPLIER PART NUMBER 1") "1528-1104-ND"))
      (libsource (lib "1655") (part "1655"))
    )
    (comp (ref "D117")
      (value "1655")
      (footprint "WS2182b_Underside")
      (description "Ws2812b 5050 Rgb Led With Integrated Driver Chip Pack Of 10")
      (fields (field (name "MF") "Adafruit") (field (name "SUPPLIER PART NUMBER 1") "1528-1104-ND"))
      (libsource (lib "1655") (part "1655"))
    )
    (comp (ref "D118")
      (value "1655")
      (footprint "WS2182b_Underside")
      (description "Ws2812b 5050 Rgb Led With Integrated Driver Chip Pack Of 10")
      (fields (field (name "MF") "Adafruit") (field (name "SUPPLIER PART NUMBER 1") "1528-1104-ND"))
      (libsource (lib "1655") (part "1655"))
    )
    (comp (ref "D119")
      (value "1655")
      (footprint "WS2182b_Underside")
      (description "Ws2812b 5050 Rgb Led With Integrated Driver Chip Pack Of 10")
      (fields (field (name "MF") "Adafruit") (field (name "SUPPLIER PART NUMBER 1") "1528-1104-ND"))
      (libsource (lib "1655") (part "1655"))
    )
    (comp (ref "D120")
      (value "1655")
      (footprint "WS2182b_Underside")
      (description "Ws2812b 5050 Rgb Led With Integrated Driver Chip Pack Of 10")
      (fields (field (name "MF") "Adafruit") (field (name "SUPPLIER PART NUMBER 1") "1528-1104-ND"))
      (libsource (lib "1655") (part "1655"))
    )
    (comp (ref "D121")
      (value "1655")
      (footprint "WS2182b_Underside")
      (description "Ws2812b 5050 Rgb Led With Integrated Driver Chip Pack Of 10")
      (fields (field (name "MF") "Adafruit") (field (name "SUPPLIER PART NUMBER 1") "1528-1104-ND"))
      (libsource (lib "1655") (part "1655"))
    )
    (comp (ref "D122")
      (value "1655")
      (footprint "WS2182b_Underside")
      (description "Ws2812b 5050 Rgb Led With Integrated Driver Chip Pack Of 10")
      (fields (field (name "MF") "Adafruit") (field (name "SUPPLIER PART NUMBER 1") "1528-1104-ND"))
      (libsource (lib "1655") (part "1655"))
    )
    (comp (ref "D123")
      (value "1655")
      (footprint "WS2182b_Underside")
      (description "Ws2812b 5050 Rgb Led With Integrated Driver Chip Pack Of 10")
      (fields (field (name "MF") "Adafruit") (field (name "SUPPLIER PART NUMBER 1") "1528-1104-ND"))
      (libsource (lib "1655") (part "1655"))
    )
    (comp (ref "D124")
      (value "1655")
      (footprint "WS2182b_Underside")
      (description "Ws2812b 5050 Rgb Led With Integrated Driver Chip Pack Of 10")
      (fields (field (name "MF") "Adafruit") (field (name "SUPPLIER PART NUMBER 1") "1528-1104-ND"))
      (libsource (lib "1655") (part "1655"))
    )
    (comp (ref "D125")
      (value "1655")
      (footprint "WS2182b_Underside")
      (description "Ws2812b 5050 Rgb Led With Integrated Driver Chip Pack Of 10")
      (fields (field (name "MF") "Adafruit") (field (name "SUPPLIER PART NUMBER 1") "1528-1104-ND"))
      (libsource (lib "1655") (part "1655"))
    )
    (comp (ref "D126")
      (value "1655")
      (footprint "WS2182b_Underside")
      (description "Ws2812b 5050 Rgb Led With Integrated Driver Chip Pack Of 10")
      (fields (field (name "MF") "Adafruit") (field (name "SUPPLIER PART NUMBER 1") "1528-1104-ND"))
      (libsource (lib "1655") (part "1655"))
    )
    (comp (ref "D127")
      (value "1655")
      (footprint "WS2182b_Underside")
      (description "Ws2812b 5050 Rgb Led With Integrated Driver Chip Pack Of 10")
      (fields (field (name "MF") "Adafruit") (field (name "SUPPLIER PART NUMBER 1") "1528-1104-ND"))
      (libsource (lib "1655") (part "1655"))
    )
    (comp (ref "D128")
      (value "1655")
      (footprint "WS2182b_Underside")
      (description "Ws2812b 5050 Rgb Led With Integrated Driver Chip Pack Of 10")
      (fields (field (name "MF") "Adafruit") (field (name "SUPPLIER PART NUMBER 1") "1528-1104-ND"))
      (libsource (lib "1655") (part "1655"))
    )
    (comp (ref "D129")
      (value "1655")
      (footprint "WS2182b_Underside")
      (description "Ws2812b 5050 Rgb Led With Integrated Driver Chip Pack Of 10")
      (fields (field (name "MF") "Adafruit") (field (name "SUPPLIER PART NUMBER 1") "1528-1104-ND"))
      (libsource (lib "1655") (part "1655"))
    )
    (comp (ref "D130")
      (value "1655")
      (footprint "WS2182b_Underside")
      (description "Ws2812b 5050 Rgb Led With Integrated Driver Chip Pack Of 10")
      (fields (field (name "MF") "Adafruit") (field (name "SUPPLIER PART NUMBER 1") "1528-1104-ND"))
      (libsource (lib "1655") (part "1655"))
    )
    (comp (ref "D131")
      (value "1655")
      (footprint "WS2182b_Underside")
      (description "Ws2812b 5050 Rgb Led With Integrated Driver Chip Pack Of 10")
      (fields (field (name "MF") "Adafruit") (field (name "SUPPLIER PART NUMBER 1") "1528-1104-ND"))
      (libsource (lib "1655") (part "1655"))
    )
    (comp (ref "D132")
      (value "1655")
      (footprint "WS2182b_Underside")
      (description "Ws2812b 5050 Rgb Led With Integrated Driver Chip Pack Of 10")
      (fields (field (name "MF") "Adafruit") (field (name "SUPPLIER PART NUMBER 1") "1528-1104-ND"))
      (libsource (lib "1655") (part "1655"))
    )
    (comp (ref "D133")
      (value "1655")
      (footprint "WS2182b_Underside")
      (description "Ws2812b 5050 Rgb Led With Integrated Driver Chip Pack Of 10")
      (fields (field (name "MF") "Adafruit") (field (name "SUPPLIER PART NUMBER 1") "1528-1104-ND"))
      (libsource (lib "1655") (part "1655"))
    )
    (comp (ref "D134")
      (value "1655")
      (footprint "WS2182b_Underside")
      (description "Ws2812b 5050 Rgb Led With Integrated Driver Chip Pack Of 10")
      (fields (field (name "MF") "Adafruit") (field (name "SUPPLIER PART NUMBER 1") "1528-1104-ND"))
      (libsource (lib "1655") (part "1655"))
    )
    (comp (ref "D135")
      (value "1655")
      (footprint "WS2182b_Underside")
      (description "Ws2812b 5050 Rgb Led With Integrated Driver Chip Pack Of 10")
      (fields (field (name "MF") "Adafruit") (field (name "SUPPLIER PART NUMBER 1") "1528-1104-ND"))
      (libsource (lib "1655") (part "1655"))
    )
    (comp (ref "D136")
      (value "1655")
      (footprint "WS2182b_Underside")
      (description "Ws2812b 5050 Rgb Led With Integrated Driver Chip Pack Of 10")
      (fields (field (name "MF") "Adafruit") (field (name "SUPPLIER PART NUMBER 1") "1528-1104-ND"))
      (libsource (lib "1655") (part "1655"))
    )
    (comp (ref "D137")
      (value "1655")
      (footprint "WS2182b_Underside")
      (description "Ws2812b 5050 Rgb Led With Integrated Driver Chip Pack Of 10")
      (fields (field (name "MF") "Adafruit") (field (name "SUPPLIER PART NUMBER 1") "1528-1104-ND"))
      (libsource (lib "1655") (part "1655"))
    )
    (comp (ref "D138")
      (value "1655")
      (footprint "WS2182b_Underside")
      (description "Ws2812b 5050 Rgb Led With Integrated Driver Chip Pack Of 10")
      (fields (field (name "MF") "Adafruit") (field (name "SUPPLIER PART NUMBER 1") "1528-1104-ND"))
      (libsource (lib "1655") (part "1655"))
    )
    (comp (ref "D139")
      (value "1655")
      (footprint "WS2182b_Underside")
      (description "Ws2812b 5050 Rgb Led With Integrated Driver Chip Pack Of 10")
      (fields (field (name "MF") "Adafruit") (field (name "SUPPLIER PART NUMBER 1") "1528-1104-ND"))
      (libsource (lib "1655") (part "1655"))
    )
    (comp (ref "D140")
      (value "1655")
      (footprint "WS2182b_Underside")
      (description "Ws2812b 5050 Rgb Led With Integrated Driver Chip Pack Of 10")
      (fields (field (name "MF") "Adafruit") (field (name "SUPPLIER PART NUMBER 1") "1528-1104-ND"))
      (libsource (lib "1655") (part "1655"))
    )
    (comp (ref "D141")
      (value "1655")
      (footprint "WS2182b_Underside")
      (description "Ws2812b 5050 Rgb Led With Integrated Driver Chip Pack Of 10")
      (fields (field (name "MF") "Adafruit") (field (name "SUPPLIER PART NUMBER 1") "1528-1104-ND"))
      (libsource (lib "1655") (part "1655"))
    )
    (comp (ref "D142")
      (value "1655")
      (footprint "WS2182b_Underside")
      (description "Ws2812b 5050 Rgb Led With Integrated Driver Chip Pack Of 10")
      (fields (field (name "MF") "Adafruit") (field (name "SUPPLIER PART NUMBER 1") "1528-1104-ND"))
      (libsource (lib "1655") (part "1655"))
    )
    (comp (ref "D143")
      (value "1655")
      (footprint "WS2182b_Underside")
      (description "Ws2812b 5050 Rgb Led With Integrated Driver Chip Pack Of 10")
      (fields (field (name "MF") "Adafruit") (field (name "SUPPLIER PART NUMBER 1") "1528-1104-ND"))
      (libsource (lib "1655") (part "1655"))
    )
    (comp (ref "D144")
      (value "1655")
      (footprint "WS2182b_Underside")
      (description "Ws2812b 5050 Rgb Led With Integrated Driver Chip Pack Of 10")
      (fields (field (name "MF") "Adafruit") (field (name "SUPPLIER PART NUMBER 1") "1528-1104-ND"))
      (libsource (lib "1655") (part "1655"))
    )
    (comp (ref "D145")
      (value "1655")
      (footprint "WS2182b_Underside")
      (description "Ws2812b 5050 Rgb Led With Integrated Driver Chip Pack Of 10")
      (fields (field (name "MF") "Adafruit") (field (name "SUPPLIER PART NUMBER 1") "1528-1104-ND"))
      (libsource (lib "1655") (part "1655"))
    )
    (comp (ref "D146")
      (value "1655")
      (footprint "WS2182b_Underside")
      (description "Ws2812b 5050 Rgb Led With Integrated Driver Chip Pack Of 10")
      (fields (field (name "MF") "Adafruit") (field (name "SUPPLIER PART NUMBER 1") "1528-1104-ND"))
      (libsource (lib "1655") (part "1655"))
    )
    (comp (ref "D147")
      (value "1655")
      (footprint "WS2182b_Underside")
      (description "Ws2812b 5050 Rgb Led With Integrated Driver Chip Pack Of 10")
      (fields (field (name "MF") "Adafruit") (field (name "SUPPLIER PART NUMBER 1") "1528-1104-ND"))
      (libsource (lib "1655") (part "1655"))
    )
    (comp (ref "D148")
      (value "1655")
      (footprint "WS2182b_Underside")
      (description "Ws2812b 5050 Rgb Led With Integrated Driver Chip Pack Of 10")
      (fields (field (name "MF") "Adafruit") (field (name "SUPPLIER PART NUMBER 1") "1528-1104-ND"))
      (libsource (lib "1655") (part "1655"))
    )
    (comp (ref "D149")
      (value "1655")
      (footprint "WS2182b_Underside")
      (description "Ws2812b 5050 Rgb Led With Integrated Driver Chip Pack Of 10")
      (fields (field (name "MF") "Adafruit") (field (name "SUPPLIER PART NUMBER 1") "1528-1104-ND"))
      (libsource (lib "1655") (part "1655"))
    )
    (comp (ref "D150")
      (value "1655")
      (footprint "WS2182b_Underside")
      (description "Ws2812b 5050 Rgb Led With Integrated Driver Chip Pack Of 10")
      (fields (field (name "MF") "Adafruit") (field (name "SUPPLIER PART NUMBER 1") "1528-1104-ND"))
      (libsource (lib "1655") (part "1655"))
    )
    (comp (ref "D151")
      (value "1655")
      (footprint "WS2182b_Underside")
      (description "Ws2812b 5050 Rgb Led With Integrated Driver Chip Pack Of 10")
      (fields (field (name "MF") "Adafruit") (field (name "SUPPLIER PART NUMBER 1") "1528-1104-ND"))
      (libsource (lib "1655") (part "1655"))
    )
    (comp (ref "D152")
      (value "1655")
      (footprint "WS2182b_Underside")
      (description "Ws2812b 5050 Rgb Led With Integrated Driver Chip Pack Of 10")
      (fields (field (name "MF") "Adafruit") (field (name "SUPPLIER PART NUMBER 1") "1528-1104-ND"))
      (libsource (lib "1655") (part "1655"))
    )
    (comp (ref "D153")
      (value "1655")
      (footprint "WS2182b_Underside")
      (description "Ws2812b 5050 Rgb Led With Integrated Driver Chip Pack Of 10")
      (fields (field (name "MF") "Adafruit") (field (name "SUPPLIER PART NUMBER 1") "1528-1104-ND"))
      (libsource (lib "1655") (part "1655"))
    )
    (comp (ref "D154")
      (value "1655")
      (footprint "WS2182b_Underside")
      (description "Ws2812b 5050 Rgb Led With Integrated Driver Chip Pack Of 10")
      (fields (field (name "MF") "Adafruit") (field (name "SUPPLIER PART NUMBER 1") "1528-1104-ND"))
      (libsource (lib "1655") (part "1655"))
    )
    (comp (ref "D155")
      (value "1655")
      (footprint "WS2182b_Underside")
      (description "Ws2812b 5050 Rgb Led With Integrated Driver Chip Pack Of 10")
      (fields (field (name "MF") "Adafruit") (field (name "SUPPLIER PART NUMBER 1") "1528-1104-ND"))
      (libsource (lib "1655") (part "1655"))
    )
    (comp (ref "D156")
      (value "1655")
      (footprint "WS2182b_Underside")
      (description "Ws2812b 5050 Rgb Led With Integrated Driver Chip Pack Of 10")
      (fields (field (name "MF") "Adafruit") (field (name "SUPPLIER PART NUMBER 1") "1528-1104-ND"))
      (libsource (lib "1655") (part "1655"))
    )
    (comp (ref "D157")
      (value "1655")
      (footprint "WS2182b_Underside")
      (description "Ws2812b 5050 Rgb Led With Integrated Driver Chip Pack Of 10")
      (fields (field (name "MF") "Adafruit") (field (name "SUPPLIER PART NUMBER 1") "1528-1104-ND"))
      (libsource (lib "1655") (part "1655"))
    )
    (comp (ref "D158")
      (value "1655")
      (footprint "WS2182b_Underside")
      (description "Ws2812b 5050 Rgb Led With Integrated Driver Chip Pack Of 10")
      (fields (field (name "MF") "Adafruit") (field (name "SUPPLIER PART NUMBER 1") "1528-1104-ND"))
      (libsource (lib "1655") (part "1655"))
    )
    (comp (ref "D159")
      (value "1655")
      (footprint "WS2182b_Underside")
      (description "Ws2812b 5050 Rgb Led With Integrated Driver Chip Pack Of 10")
      (fields (field (name "MF") "Adafruit") (field (name "SUPPLIER PART NUMBER 1") "1528-1104-ND"))
      (libsource (lib "1655") (part "1655"))
    )
    (comp (ref "D160")
      (value "1655")
      (footprint "WS2182b_Underside")
      (description "Ws2812b 5050 Rgb Led With Integrated Driver Chip Pack Of 10")
      (fields (field (name "MF") "Adafruit") (field (name "SUPPLIER PART NUMBER 1") "1528-1104-ND"))
      (libsource (lib "1655") (part "1655"))
    )
    (comp (ref "D161")
      (value "1655")
      (footprint "WS2182b_Underside")
      (description "Ws2812b 5050 Rgb Led With Integrated Driver Chip Pack Of 10")
      (fields (field (name "MF") "Adafruit") (field (name "SUPPLIER PART NUMBER 1") "1528-1104-ND"))
      (libsource (lib "1655") (part "1655"))
    )
    (comp (ref "D162")
      (value "1655")
      (footprint "WS2182b_Underside")
      (description "Ws2812b 5050 Rgb Led With Integrated Driver Chip Pack Of 10")
      (fields (field (name "MF") "Adafruit") (field (name "SUPPLIER PART NUMBER 1") "1528-1104-ND"))
      (libsource (lib "1655") (part "1655"))
    )
    (comp (ref "D163")
      (value "1655")
      (footprint "WS2182b_Underside")
      (description "Ws2812b 5050 Rgb Led With Integrated Driver Chip Pack Of 10")
      (fields (field (name "MF") "Adafruit") (field (name "SUPPLIER PART NUMBER 1") "1528-1104-ND"))
      (libsource (lib "1655") (part "1655"))
    )
    (comp (ref "D164")
      (value "1655")
      (footprint "WS2182b_Underside")
      (description "Ws2812b 5050 Rgb Led With Integrated Driver Chip Pack Of 10")
      (fields (field (name "MF") "Adafruit") (field (name "SUPPLIER PART NUMBER 1") "1528-1104-ND"))
      (libsource (lib "1655") (part "1655"))
    )
    (comp (ref "D165")
      (value "1655")
      (footprint "WS2182b_Underside")
      (description "Ws2812b 5050 Rgb Led With Integrated Driver Chip Pack Of 10")
      (fields (field (name "MF") "Adafruit") (field (name "SUPPLIER PART NUMBER 1") "1528-1104-ND"))
      (libsource (lib "1655") (part "1655"))
    )
    (comp (ref "D166")
      (value "1655")
      (footprint "WS2182b_Underside")
      (description "Ws2812b 5050 Rgb Led With Integrated Driver Chip Pack Of 10")
      (fields (field (name "MF") "Adafruit") (field (name "SUPPLIER PART NUMBER 1") "1528-1104-ND"))
      (libsource (lib "1655") (part "1655"))
    )
    (comp (ref "D167")
      (value "1655")
      (footprint "WS2182b_Underside")
      (description "Ws2812b 5050 Rgb Led With Integrated Driver Chip Pack Of 10")
      (fields (field (name "MF") "Adafruit") (field (name "SUPPLIER PART NUMBER 1") "1528-1104-ND"))
      (libsource (lib "1655") (part "1655"))
    )
    (comp (ref "D168")
      (value "1655")
      (footprint "WS2182b_Underside")
      (description "Ws2812b 5050 Rgb Led With Integrated Driver Chip Pack Of 10")
      (fields (field (name "MF") "Adafruit") (field (name "SUPPLIER PART NUMBER 1") "1528-1104-ND"))
      (libsource (lib "1655") (part "1655"))
    )
    (comp (ref "D169")
      (value "1655")
      (footprint "WS2182b_Underside")
      (description "Ws2812b 5050 Rgb Led With Integrated Driver Chip Pack Of 10")
      (fields (field (name "MF") "Adafruit") (field (name "SUPPLIER PART NUMBER 1") "1528-1104-ND"))
      (libsource (lib "1655") (part "1655"))
    )
    (comp (ref "D170")
      (value "1655")
      (footprint "WS2182b_Underside")
      (description "Ws2812b 5050 Rgb Led With Integrated Driver Chip Pack Of 10")
      (fields (field (name "MF") "Adafruit") (field (name "SUPPLIER PART NUMBER 1") "1528-1104-ND"))
      (libsource (lib "1655") (part "1655"))
    )
    (comp (ref "D171")
      (value "1655")
      (footprint "WS2182b_Underside")
      (description "Ws2812b 5050 Rgb Led With Integrated Driver Chip Pack Of 10")
      (fields (field (name "MF") "Adafruit") (field (name "SUPPLIER PART NUMBER 1") "1528-1104-ND"))
      (libsource (lib "1655") (part "1655"))
    )
    (comp (ref "D172")
      (value "1655")
      (footprint "WS2182b_Underside")
      (description "Ws2812b 5050 Rgb Led With Integrated Driver Chip Pack Of 10")
      (fields (field (name "MF") "Adafruit") (field (name "SUPPLIER PART NUMBER 1") "1528-1104-ND"))
      (libsource (lib "1655") (part "1655"))
    )
    (comp (ref "D173")
      (value "1655")
      (footprint "WS2182b_Underside")
      (description "Ws2812b 5050 Rgb Led With Integrated Driver Chip Pack Of 10")
      (fields (field (name "MF") "Adafruit") (field (name "SUPPLIER PART NUMBER 1") "1528-1104-ND"))
      (libsource (lib "1655") (part "1655"))
    )
    (comp (ref "U12")
      (value "SN74LV1T34DBVR")
      (footprint "SOT95P280X145-5N")
      (description "Single Power Supply BUFFER Logic Level Shifter _no enable_ 5-SOT-23 -40 to 125")
      (fields (field (name "MF") "Texas Instruments"))
      (libsource (lib "SN74LV1T34DBVR") (part "SN74LV1T34DBVR"))
    )
  )
  (nets
    (net (code "1") (name "/VDD") (class "Default")
      (node (ref "C100") (pin "1") (pinfunction "1_1") (pintype "passive"))
      (node (ref "C17") (pin "1") (pinfunction "1_1") (pintype "passive"))
      (node (ref "C18") (pin "1") (pinfunction "1_1") (pintype "passive"))
      (node (ref "C19") (pin "1") (pinfunction "1_1") (pintype "passive"))
      (node (ref "C20") (pin "1") (pinfunction "1_1") (pintype "passive"))
      (node (ref "C21") (pin "1") (pinfunction "1_1") (pintype "passive"))
      (node (ref "C22") (pin "1") (pinfunction "1_1") (pintype "passive"))
      (node (ref "C23") (pin "1") (pinfunction "1_1") (pintype "passive"))
      (node (ref "C24") (pin "1") (pinfunction "1_1") (pintype "passive"))
      (node (ref "C25") (pin "1") (pinfunction "1_1") (pintype "passive"))
      (node (ref "C26") (pin "1") (pinfunction "1_1") (pintype "passive"))
      (node (ref "C27") (pin "1") (pinfunction "1_1") (pintype "passive"))
      (node (ref "C28") (pin "1") (pinfunction "1_1") (pintype "passive"))
      (node (ref "C29") (pin "1") (pinfunction "1_1") (pintype "passive"))
      (node (ref "C30") (pin "1") (pinfunction "1_1") (pintype "passive"))
      (node (ref "C31") (pin "1") (pinfunction "1_1") (pintype "passive"))
      (node (ref "C32") (pin "1") (pinfunction "1_1") (pintype "passive"))
      (node (ref "C33") (pin "1") (pinfunction "1_1") (pintype "passive"))
      (node (ref "C34") (pin "1") (pinfunction "1_1") (pintype "passive"))
      (node (ref "C35") (pin "1") (pinfunction "1_1") (pintype "passive"))
      (node (ref "C36") (pin "1") (pinfunction "1_1") (pintype "passive"))
      (node (ref "C37") (pin "1") (pinfunction "1_1") (pintype "passive"))
      (node (ref "C38") (pin "1") (pinfunction "1_1") (pintype "passive"))
      (node (ref "C39") (pin "1") (pinfunction "1_1") (pintype "passive"))
      (node (ref "C40") (pin "1") (pinfunction "1_1") (pintype "passive"))
      (node (ref "C41") (pin "1") (pinfunction "1_1") (pintype "passive"))
      (node (ref "C42") (pin "1") (pinfunction "1_1") (pintype "passive"))
      (node (ref "C43") (pin "1") (pinfunction "1_1") (pintype "passive"))
      (node (ref "C45") (pin "1") (pinfunction "1_1") (pintype "passive"))
      (node (ref "C46") (pin "1") (pinfunction "1_1") (pintype "passive"))
      (node (ref "C47") (pin "1") (pinfunction "1_1") (pintype "passive"))
      (node (ref "C48") (pin "1") (pinfunction "1_1") (pintype "passive"))
      (node (ref "C49") (pin "1") (pinfunction "1_1") (pintype "passive"))
      (node (ref "C50") (pin "1") (pinfunction "1_1") (pintype "passive"))
      (node (ref "C51") (pin "1") (pinfunction "1_1") (pintype "passive"))
      (node (ref "C52") (pin "1") (pinfunction "1_1") (pintype "passive"))
      (node (ref "C53") (pin "1") (pinfunction "1_1") (pintype "passive"))
      (node (ref "C54") (pin "1") (pinfunction "1_1") (pintype "passive"))
      (node (ref "C55") (pin "1") (pinfunction "1_1") (pintype "passive"))
      (node (ref "C56") (pin "1") (pinfunction "1_1") (pintype "passive"))
      (node (ref "C57") (pin "1") (pinfunction "1_1") (pintype "passive"))
      (node (ref "C58") (pin "1") (pinfunction "1_1") (pintype "passive"))
      (node (ref "C59") (pin "1") (pinfunction "1_1") (pintype "passive"))
      (node (ref "C60") (pin "1") (pinfunction "1_1") (pintype "passive"))
      (node (ref "C62") (pin "1") (pinfunction "1_1") (pintype "passive"))
      (node (ref "C63") (pin "1") (pinfunction "1_1") (pintype "passive"))
      (node (ref "C64") (pin "1") (pinfunction "1_1") (pintype "passive"))
      (node (ref "C65") (pin "1") (pinfunction "1_1") (pintype "passive"))
      (node (ref "C66") (pin "1") (pinfunction "1_1") (pintype "passive"))
      (node (ref "C67") (pin "1") (pinfunction "1_1") (pintype "passive"))
      (node (ref "C68") (pin "1") (pinfunction "1_1") (pintype "passive"))
      (node (ref "C69") (pin "1") (pinfunction "1_1") (pintype "passive"))
      (node (ref "C70") (pin "1") (pinfunction "1_1") (pintype "passive"))
      (node (ref "C71") (pin "1") (pinfunction "1_1") (pintype "passive"))
      (node (ref "C72") (pin "1") (pinfunction "1_1") (pintype "passive"))
      (node (ref "C73") (pin "1") (pinfunction "1_1") (pintype "passive"))
      (node (ref "C74") (pin "1") (pinfunction "1_1") (pintype "passive"))
      (node (ref "C75") (pin "1") (pinfunction "1_1") (pintype "passive"))
      (node (ref "C76") (pin "1") (pinfunction "1_1") (pintype "passive"))
      (node (ref "C77") (pin "1") (pinfunction "1_1") (pintype "passive"))
      (node (ref "C79") (pin "1") (pinfunction "1_1") (pintype "passive"))
      (node (ref "C80") (pin "1") (pinfunction "1_1") (pintype "passive"))
      (node (ref "C81") (pin "1") (pinfunction "1_1") (pintype "passive"))
      (node (ref "C82") (pin "1") (pinfunction "1_1") (pintype "passive"))
      (node (ref "C83") (pin "1") (pinfunction "1_1") (pintype "passive"))
      (node (ref "C84") (pin "1") (pinfunction "1_1") (pintype "passive"))
      (node (ref "C85") (pin "1") (pinfunction "1_1") (pintype "passive"))
      (node (ref "C86") (pin "1") (pinfunction "1_1") (pintype "passive"))
      (node (ref "C87") (pin "1") (pinfunction "1_1") (pintype "passive"))
      (node (ref "C88") (pin "1") (pinfunction "1_1") (pintype "passive"))
      (node (ref "C89") (pin "1") (pinfunction "1_1") (pintype "passive"))
      (node (ref "C90") (pin "1") (pinfunction "1_1") (pintype "passive"))
      (node (ref "C92") (pin "1") (pinfunction "1_1") (pintype "passive"))
      (node (ref "C93") (pin "1") (pinfunction "1_1") (pintype "passive"))
      (node (ref "C94") (pin "1") (pinfunction "1_1") (pintype "passive"))
      (node (ref "C95") (pin "1") (pinfunction "1_1") (pintype "passive"))
      (node (ref "C96") (pin "1") (pinfunction "1_1") (pintype "passive"))
      (node (ref "C97") (pin "1") (pinfunction "1_1") (pintype "passive"))
      (node (ref "C98") (pin "1") (pinfunction "1_1") (pintype "passive"))
      (node (ref "C99") (pin "1") (pinfunction "1_1") (pintype "passive"))
      (node (ref "D100") (pin "1") (pinfunction "VDD_1") (pintype "power_in"))
      (node (ref "D101") (pin "1") (pinfunction "VDD_1") (pintype "power_in"))
      (node (ref "D102") (pin "1") (pinfunction "VDD_1") (pintype "power_in"))
      (node (ref "D103") (pin "1") (pinfunction "VDD_1") (pintype "power_in"))
      (node (ref "D104") (pin "1") (pinfunction "VDD_1") (pintype "power_in"))
      (node (ref "D105") (pin "1") (pinfunction "VDD_1") (pintype "power_in"))
      (node (ref "D106") (pin "1") (pinfunction "VDD_1") (pintype "power_in"))
      (node (ref "D107") (pin "1") (pinfunction "VDD_1") (pintype "power_in"))
      (node (ref "D108") (pin "1") (pinfunction "VDD_1") (pintype "power_in"))
      (node (ref "D109") (pin "1") (pinfunction "VDD_1") (pintype "power_in"))
      (node (ref "D110") (pin "1") (pinfunction "VDD_1") (pintype "power_in"))
      (node (ref "D111") (pin "1") (pinfunction "VDD_1") (pintype "power_in"))
      (node (ref "D112") (pin "1") (pinfunction "VDD_1") (pintype "power_in"))
      (node (ref "D113") (pin "1") (pinfunction "VDD_1") (pintype "power_in"))
      (node (ref "D114") (pin "1") (pinfunction "VDD_1") (pintype "power_in"))
      (node (ref "D115") (pin "1") (pinfunction "VDD_1") (pintype "power_in"))
      (node (ref "D116") (pin "1") (pinfunction "VDD_1") (pintype "power_in"))
      (node (ref "D118") (pin "1") (pinfunction "VDD_1") (pintype "power_in"))
      (node (ref "D119") (pin "1") (pinfunction "VDD_1") (pintype "power_in"))
      (node (ref "D120") (pin "1") (pinfunction "VDD_1") (pintype "power_in"))
      (node (ref "D121") (pin "1") (pinfunction "VDD_1") (pintype "power_in"))
      (node (ref "D122") (pin "1") (pinfunction "VDD_1") (pintype "power_in"))
      (node (ref "D123") (pin "1") (pinfunction "VDD_1") (pintype "power_in"))
      (node (ref "D124") (pin "1") (pinfunction "VDD_1") (pintype "power_in"))
      (node (ref "D125") (pin "1") (pinfunction "VDD_1") (pintype "power_in"))
      (node (ref "D126") (pin "1") (pinfunction "VDD_1") (pintype "power_in"))
      (node (ref "D127") (pin "1") (pinfunction "VDD_1") (pintype "power_in"))
      (node (ref "D128") (pin "1") (pinfunction "VDD_1") (pintype "power_in"))
      (node (ref "D129") (pin "1") (pinfunction "VDD_1") (pintype "power_in"))
      (node (ref "D130") (pin "1") (pinfunction "VDD_1") (pintype "power_in"))
      (node (ref "D131") (pin "1") (pinfunction "VDD_1") (pintype "power_in"))
      (node (ref "D132") (pin "1") (pinfunction "VDD_1") (pintype "power_in"))
      (node (ref "D133") (pin "1") (pinfunction "VDD_1") (pintype "power_in"))
      (node (ref "D135") (pin "1") (pinfunction "VDD_1") (pintype "power_in"))
      (node (ref "D136") (pin "1") (pinfunction "VDD_1") (pintype "power_in"))
      (node (ref "D137") (pin "1") (pinfunction "VDD_1") (pintype "power_in"))
      (node (ref "D138") (pin "1") (pinfunction "VDD_1") (pintype "power_in"))
      (node (ref "D139") (pin "1") (pinfunction "VDD_1") (pintype "power_in"))
      (node (ref "D140") (pin "1") (pinfunction "VDD_1") (pintype "power_in"))
      (node (ref "D141") (pin "1") (pinfunction "VDD_1") (pintype "power_in"))
      (node (ref "D142") (pin "1") (pinfunction "VDD_1") (pintype "power_in"))
      (node (ref "D143") (pin "1") (pinfunction "VDD_1") (pintype "power_in"))
      (node (ref "D144") (pin "1") (pinfunction "VDD_1") (pintype "power_in"))
      (node (ref "D145") (pin "1") (pinfunction "VDD_1") (pintype "power_in"))
      (node (ref "D146") (pin "1") (pinfunction "VDD_1") (pintype "power_in"))
      (node (ref "D147") (pin "1") (pinfunction "VDD_1") (pintype "power_in"))
      (node (ref "D148") (pin "1") (pinfunction "VDD_1") (pintype "power_in"))
      (node (ref "D149") (pin "1") (pinfunction "VDD_1") (pintype "power_in"))
      (node (ref "D150") (pin "1") (pinfunction "VDD_1") (pintype "power_in"))
      (node (ref "D152") (pin "1") (pinfunction "VDD_1") (pintype "power_in"))
      (node (ref "D153") (pin "1") (pinfunction "VDD_1") (pintype "power_in"))
      (node (ref "D154") (pin "1") (pinfunction "VDD_1") (pintype "power_in"))
      (node (ref "D155") (pin "1") (pinfunction "VDD_1") (pintype "power_in"))
      (node (ref "D156") (pin "1") (pinfunction "VDD_1") (pintype "power_in"))
      (node (ref "D157") (pin "1") (pinfunction "VDD_1") (pintype "power_in"))
      (node (ref "D158") (pin "1") (pinfunction "VDD_1") (pintype "power_in"))
      (node (ref "D159") (pin "1") (pinfunction "VDD_1") (pintype "power_in"))
      (node (ref "D160") (pin "1") (pinfunction "VDD_1") (pintype "power_in"))
      (node (ref "D161") (pin "1") (pinfunction "VDD_1") (pintype "power_in"))
      (node (ref "D162") (pin "1") (pinfunction "VDD_1") (pintype "power_in"))
      (node (ref "D163") (pin "1") (pinfunction "VDD_1") (pintype "power_in"))
      (node (ref "D165") (pin "1") (pinfunction "VDD_1") (pintype "power_in"))
      (node (ref "D166") (pin "1") (pinfunction "VDD_1") (pintype "power_in"))
      (node (ref "D167") (pin "1") (pinfunction "VDD_1") (pintype "power_in"))
      (node (ref "D168") (pin "1") (pinfunction "VDD_1") (pintype "power_in"))
      (node (ref "D169") (pin "1") (pinfunction "VDD_1") (pintype "power_in"))
      (node (ref "D170") (pin "1") (pinfunction "VDD_1") (pintype "power_in"))
      (node (ref "D171") (pin "1") (pinfunction "VDD_1") (pintype "power_in"))
      (node (ref "D172") (pin "1") (pinfunction "VDD_1") (pintype "power_in"))
      (node (ref "D173") (pin "1") (pinfunction "VDD_1") (pintype "power_in"))
      (node (ref "D90") (pin "1") (pinfunction "VDD_1") (pintype "power_in"))
      (node (ref "D91") (pin "1") (pinfunction "VDD_1") (pintype "power_in"))
      (node (ref "D92") (pin "1") (pinfunction "VDD_1") (pintype "power_in"))
      (node (ref "D93") (pin "1") (pinfunction "VDD_1") (pintype "power_in"))
      (node (ref "D94") (pin "1") (pinfunction "VDD_1") (pintype "power_in"))
      (node (ref "D95") (pin "1") (pinfunction "VDD_1") (pintype "power_in"))
      (node (ref "D96") (pin "1") (pinfunction "VDD_1") (pintype "power_in"))
      (node (ref "D97") (pin "1") (pinfunction "VDD_1") (pintype "power_in"))
      (node (ref "D98") (pin "1") (pinfunction "VDD_1") (pintype "power_in"))
      (node (ref "D99") (pin "1") (pinfunction "VDD_1") (pintype "power_in"))
      (node (ref "U12") (pin "5") (pinfunction "VCC_5") (pintype "power_in"))
    )
    (net (code "2") (name "GND") (class "Default")
      (node (ref "C100") (pin "2") (pinfunction "2_2") (pintype "passive"))
      (node (ref "C17") (pin "2") (pinfunction "2_2") (pintype "passive"))
      (node (ref "C18") (pin "2") (pinfunction "2_2") (pintype "passive"))
      (node (ref "C19") (pin "2") (pinfunction "2_2") (pintype "passive"))
      (node (ref "C20") (pin "2") (pinfunction "2_2") (pintype "passive"))
      (node (ref "C21") (pin "2") (pinfunction "2_2") (pintype "passive"))
      (node (ref "C22") (pin "2") (pinfunction "2_2") (pintype "passive"))
      (node (ref "C23") (pin "2") (pinfunction "2_2") (pintype "passive"))
      (node (ref "C24") (pin "2") (pinfunction "2_2") (pintype "passive"))
      (node (ref "C25") (pin "2") (pinfunction "2_2") (pintype "passive"))
      (node (ref "C26") (pin "2") (pinfunction "2_2") (pintype "passive"))
      (node (ref "C27") (pin "2") (pinfunction "2_2") (pintype "passive"))
      (node (ref "C30") (pin "2") (pinfunction "2_2") (pintype "passive"))
      (node (ref "C31") (pin "2") (pinfunction "2_2") (pintype "passive"))
      (node (ref "C32") (pin "2") (pinfunction "2_2") (pintype "passive"))
      (node (ref "C33") (pin "2") (pinfunction "2_2") (pintype "passive"))
      (node (ref "C34") (pin "2") (pinfunction "2_2") (pintype "passive"))
      (node (ref "C35") (pin "2") (pinfunction "2_2") (pintype "passive"))
      (node (ref "C36") (pin "2") (pinfunction "2_2") (pintype "passive"))
      (node (ref "C37") (pin "2") (pinfunction "2_2") (pintype "passive"))
      (node (ref "C38") (pin "2") (pinfunction "2_2") (pintype "passive"))
      (node (ref "C39") (pin "2") (pinfunction "2_2") (pintype "passive"))
      (node (ref "C40") (pin "2") (pinfunction "2_2") (pintype "passive"))
      (node (ref "C41") (pin "2") (pinfunction "2_2") (pintype "passive"))
      (node (ref "C42") (pin "2") (pinfunction "2_2") (pintype "passive"))
      (node (ref "C43") (pin "2") (pinfunction "2_2") (pintype "passive"))
      (node (ref "C46") (pin "2") (pinfunction "2_2") (pintype "passive"))
      (node (ref "C47") (pin "2") (pinfunction "2_2") (pintype "passive"))
      (node (ref "C48") (pin "2") (pinfunction "2_2") (pintype "passive"))
      (node (ref "C49") (pin "2") (pinfunction "2_2") (pintype "passive"))
      (node (ref "C50") (pin "2") (pinfunction "2_2") (pintype "passive"))
      (node (ref "C51") (pin "2") (pinfunction "2_2") (pintype "passive"))
      (node (ref "C52") (pin "2") (pinfunction "2_2") (pintype "passive"))
      (node (ref "C53") (pin "2") (pinfunction "2_2") (pintype "passive"))
      (node (ref "C54") (pin "2") (pinfunction "2_2") (pintype "passive"))
      (node (ref "C55") (pin "2") (pinfunction "2_2") (pintype "passive"))
      (node (ref "C56") (pin "2") (pinfunction "2_2") (pintype "passive"))
      (node (ref "C57") (pin "2") (pinfunction "2_2") (pintype "passive"))
      (node (ref "C58") (pin "2") (pinfunction "2_2") (pintype "passive"))
      (node (ref "C59") (pin "2") (pinfunction "2_2") (pintype "passive"))
      (node (ref "C60") (pin "2") (pinfunction "2_2") (pintype "passive"))
      (node (ref "C63") (pin "2") (pinfunction "2_2") (pintype "passive"))
      (node (ref "C64") (pin "2") (pinfunction "2_2") (pintype "passive"))
      (node (ref "C65") (pin "2") (pinfunction "2_2") (pintype "passive"))
      (node (ref "C66") (pin "2") (pinfunction "2_2") (pintype "passive"))
      (node (ref "C67") (pin "2") (pinfunction "2_2") (pintype "passive"))
      (node (ref "C68") (pin "2") (pinfunction "2_2") (pintype "passive"))
      (node (ref "C69") (pin "2") (pinfunction "2_2") (pintype "passive"))
      (node (ref "C70") (pin "2") (pinfunction "2_2") (pintype "passive"))
      (node (ref "C71") (pin "2") (pinfunction "2_2") (pintype "passive"))
      (node (ref "C72") (pin "2") (pinfunction "2_2") (pintype "passive"))
      (node (ref "C73") (pin "2") (pinfunction "2_2") (pintype "passive"))
      (node (ref "C74") (pin "2") (pinfunction "2_2") (pintype "passive"))
      (node (ref "C75") (pin "2") (pinfunction "2_2") (pintype "passive"))
      (node (ref "C76") (pin "2") (pinfunction "2_2") (pintype "passive"))
      (node (ref "C80") (pin "2") (pinfunction "2_2") (pintype "passive"))
      (node (ref "C81") (pin "2") (pinfunction "2_2") (pintype "passive"))
      (node (ref "C82") (pin "2") (pinfunction "2_2") (pintype "passive"))
      (node (ref "C83") (pin "2") (pinfunction "2_2") (pintype "passive"))
      (node (ref "C84") (pin "2") (pinfunction "2_2") (pintype "passive"))
      (node (ref "C85") (pin "2") (pinfunction "2_2") (pintype "passive"))
      (node (ref "C86") (pin "2") (pinfunction "2_2") (pintype "passive"))
      (node (ref "C87") (pin "2") (pinfunction "2_2") (pintype "passive"))
      (node (ref "C88") (pin "2") (pinfunction "2_2") (pintype "passive"))
      (node (ref "C89") (pin "2") (pinfunction "2_2") (pintype "passive"))
      (node (ref "C90") (pin "2") (pinfunction "2_2") (pintype "passive"))
      (node (ref "C93") (pin "2") (pinfunction "2_2") (pintype "passive"))
      (node (ref "C94") (pin "2") (pinfunction "2_2") (pintype "passive"))
      (node (ref "C95") (pin "2") (pinfunction "2_2") (pintype "passive"))
      (node (ref "C96") (pin "2") (pinfunction "2_2") (pintype "passive"))
      (node (ref "C97") (pin "2") (pinfunction "2_2") (pintype "passive"))
      (node (ref "C98") (pin "2") (pinfunction "2_2") (pintype "passive"))
      (node (ref "C99") (pin "2") (pinfunction "2_2") (pintype "passive"))
      (node (ref "D100") (pin "3") (pinfunction "VSS_3") (pintype "passive"))
      (node (ref "D103") (pin "3") (pinfunction "VSS_3") (pintype "passive"))
      (node (ref "D104") (pin "3") (pinfunction "VSS_3") (pintype "passive"))
      (node (ref "D105") (pin "3") (pinfunction "VSS_3") (pintype "passive"))
      (node (ref "D106") (pin "3") (pinfunction "VSS_3") (pintype "passive"))
      (node (ref "D107") (pin "3") (pinfunction "VSS_3") (pintype "passive"))
      (node (ref "D108") (pin "3") (pinfunction "VSS_3") (pintype "passive"))
      (node (ref "D109") (pin "3") (pinfunction "VSS_3") (pintype "passive"))
      (node (ref "D110") (pin "3") (pinfunction "VSS_3") (pintype "passive"))
      (node (ref "D111") (pin "3") (pinfunction "VSS_3") (pintype "passive"))
      (node (ref "D112") (pin "3") (pinfunction "VSS_3") (pintype "passive"))
      (node (ref "D113") (pin "3") (pinfunction "VSS_3") (pintype "passive"))
      (node (ref "D114") (pin "3") (pinfunction "VSS_3") (pintype "passive"))
      (node (ref "D115") (pin "3") (pinfunction "VSS_3") (pintype "passive"))
      (node (ref "D116") (pin "3") (pinfunction "VSS_3") (pintype "passive"))
      (node (ref "D119") (pin "3") (pinfunction "VSS_3") (pintype "passive"))
      (node (ref "D120") (pin "3") (pinfunction "VSS_3") (pintype "passive"))
      (node (ref "D121") (pin "3") (pinfunction "VSS_3") (pintype "passive"))
      (node (ref "D122") (pin "3") (pinfunction "VSS_3") (pintype "passive"))
      (node (ref "D123") (pin "3") (pinfunction "VSS_3") (pintype "passive"))
      (node (ref "D124") (pin "3") (pinfunction "VSS_3") (pintype "passive"))
      (node (ref "D125") (pin "3") (pinfunction "VSS_3") (pintype "passive"))
      (node (ref "D126") (pin "3") (pinfunction "VSS_3") (pintype "passive"))
      (node (ref "D127") (pin "3") (pinfunction "VSS_3") (pintype "passive"))
      (node (ref "D128") (pin "3") (pinfunction "VSS_3") (pintype "passive"))
      (node (ref "D129") (pin "3") (pinfunction "VSS_3") (pintype "passive"))
      (node (ref "D130") (pin "3") (pinfunction "VSS_3") (pintype "passive"))
      (node (ref "D131") (pin "3") (pinfunction "VSS_3") (pintype "passive"))
      (node (ref "D132") (pin "3") (pinfunction "VSS_3") (pintype "passive"))
      (node (ref "D133") (pin "3") (pinfunction "VSS_3") (pintype "passive"))
      (node (ref "D136") (pin "3") (pinfunction "VSS_3") (pintype "passive"))
      (node (ref "D137") (pin "3") (pinfunction "VSS_3") (pintype "passive"))
      (node (ref "D138") (pin "3") (pinfunction "VSS_3") (pintype "passive"))
      (node (ref "D139") (pin "3") (pinfunction "VSS_3") (pintype "passive"))
      (node (ref "D140") (pin "3") (pinfunction "VSS_3") (pintype "passive"))
      (node (ref "D141") (pin "3") (pinfunction "VSS_3") (pintype "passive"))
      (node (ref "D142") (pin "3") (pinfunction "VSS_3") (pintype "passive"))
      (node (ref "D143") (pin "3") (pinfunction "VSS_3") (pintype "passive"))
      (node (ref "D144") (pin "3") (pinfunction "VSS_3") (pintype "passive"))
      (node (ref "D145") (pin "3") (pinfunction "VSS_3") (pintype "passive"))
      (node (ref "D146") (pin "3") (pinfunction "VSS_3") (pintype "passive"))
      (node (ref "D147") (pin "3") (pinfunction "VSS_3") (pintype "passive"))
      (node (ref "D148") (pin "3") (pinfunction "VSS_3") (pintype "passive"))
      (node (ref "D149") (pin "3") (pinfunction "VSS_3") (pintype "passive"))
      (node (ref "D150") (pin "3") (pinfunction "VSS_3") (pintype "passive"))
      (node (ref "D153") (pin "3") (pinfunction "VSS_3") (pintype "passive"))
      (node (ref "D154") (pin "3") (pinfunction "VSS_3") (pintype "passive"))
      (node (ref "D155") (pin "3") (pinfunction "VSS_3") (pintype "passive"))
      (node (ref "D156") (pin "3") (pinfunction "VSS_3") (pintype "passive"))
      (node (ref "D157") (pin "3") (pinfunction "VSS_3") (pintype "passive"))
      (node (ref "D158") (pin "3") (pinfunction "VSS_3") (pintype "passive"))
      (node (ref "D159") (pin "3") (pinfunction "VSS_3") (pintype "passive"))
      (node (ref "D160") (pin "3") (pinfunction "VSS_3") (pintype "passive"))
      (node (ref "D161") (pin "3") (pinfunction "VSS_3") (pintype "passive"))
      (node (ref "D162") (pin "3") (pinfunction "VSS_3") (pintype "passive"))
      (node (ref "D163") (pin "3") (pinfunction "VSS_3") (pintype "passive"))
      (node (ref "D166") (pin "3") (pinfunction "VSS_3") (pintype "passive"))
      (node (ref "D167") (pin "3") (pinfunction "VSS_3") (pintype "passive"))
      (node (ref "D168") (pin "3") (pinfunction "VSS_3") (pintype "passive"))
      (node (ref "D169") (pin "3") (pinfunction "VSS_3") (pintype "passive"))
      (node (ref "D170") (pin "3") (pinfunction "VSS_3") (pintype "passive"))
      (node (ref "D171") (pin "3") (pinfunction "VSS_3") (pintype "passive"))
      (node (ref "D172") (pin "3") (pinfunction "VSS_3") (pintype "passive"))
      (node (ref "D173") (pin "3") (pinfunction "VSS_3") (pintype "passive"))
      (node (ref "D90") (pin "3") (pinfunction "VSS_3") (pintype "passive"))
      (node (ref "D91") (pin "3") (pinfunction "VSS_3") (pintype "passive"))
      (node (ref "D92") (pin "3") (pinfunction "VSS_3") (pintype "passive"))
      (node (ref "D93") (pin "3") (pinfunction "VSS_3") (pintype "passive"))
      (node (ref "D94") (pin "3") (pinfunction "VSS_3") (pintype "passive"))
      (node (ref "D95") (pin "3") (pinfunction "VSS_3") (pintype "passive"))
      (node (ref "D96") (pin "3") (pinfunction "VSS_3") (pintype "passive"))
      (node (ref "D97") (pin "3") (pinfunction "VSS_3") (pintype "passive"))
      (node (ref "D98") (pin "3") (pinfunction "VSS_3") (pintype "passive"))
      (node (ref "D99") (pin "3") (pinfunction "VSS_3") (pintype "passive"))
      (node (ref "U12") (pin "3") (pinfunction "GND_3") (pintype "power_in"))
    )
    (net (code "3") (name "Net-(D90-DIN)") (class "Default")
      (node (ref "D90") (pin "4") (pinfunction "DIN_4") (pintype "input"))
      (node (ref "U12") (pin "4") (pinfunction "Y_4") (pintype "output"))
    )
    (net (code "4") (name "Net-(D90-DOUT)") (class "Default")
      (node (ref "D90") (pin "2") (pinfunction "DOUT_2") (pintype "output"))
      (node (ref "D91") (pin "4") (pinfunction "DIN_4") (pintype "input"))
    )
    (net (code "5") (name "Net-(D91-DOUT)") (class "Default")
      (node (ref "D91") (pin "2") (pinfunction "DOUT_2") (pintype "output"))
      (node (ref "D92") (pin "4") (pinfunction "DIN_4") (pintype "input"))
    )
    (net (code "6") (name "Net-(D92-DOUT)") (class "Default")
      (node (ref "D92") (pin "2") (pinfunction "DOUT_2") (pintype "output"))
      (node (ref "D93") (pin "4") (pinfunction "DIN_4") (pintype "input"))
    )
    (net (code "7") (name "Net-(D93-DOUT)") (class "Default")
      (node (ref "D93") (pin "2") (pinfunction "DOUT_2") (pintype "output"))
      (node (ref "D94") (pin "4") (pinfunction "DIN_4") (pintype "input"))
    )
    (net (code "8") (name "Net-(D94-DOUT)") (class "Default")
      (node (ref "D94") (pin "2") (pinfunction "DOUT_2") (pintype "output"))
      (node (ref "D95") (pin "4") (pinfunction "DIN_4") (pintype "input"))
    )
    (net (code "9") (name "Net-(D95-DOUT)") (class "Default")
      (node (ref "D95") (pin "2") (pinfunction "DOUT_2") (pintype "output"))
      (node (ref "D96") (pin "4") (pinfunction "DIN_4") (pintype "input"))
    )
    (net (code "10") (name "Net-(D96-DOUT)") (class "Default")
      (node (ref "D96") (pin "2") (pinfunction "DOUT_2") (pintype "output"))
      (node (ref "D97") (pin "4") (pinfunction "DIN_4") (pintype "input"))
    )
    (net (code "11") (name "Net-(D97-DOUT)") (class "Default")
      (node (ref "D97") (pin "2") (pinfunction "DOUT_2") (pintype "output"))
      (node (ref "D98") (pin "4") (pinfunction "DIN_4") (pintype "input"))
    )
    (net (code "12") (name "Net-(D98-DOUT)") (class "Default")
      (node (ref "D98") (pin "2") (pinfunction "DOUT_2") (pintype "output"))
      (node (ref "D99") (pin "4") (pinfunction "DIN_4") (pintype "input"))
    )
    (net (code "13") (name "Net-(D100-DIN)") (class "Default")
      (node (ref "D100") (pin "4") (pinfunction "DIN_4") (pintype "input"))
      (node (ref "D99") (pin "2") (pinfunction "DOUT_2") (pintype "output"))
    )
    (net (code "14") (name "Net-(D100-DOUT)") (class "Default")
      (node (ref "D100") (pin "2") (pinfunction "DOUT_2") (pintype "output"))
      (node (ref "D101") (pin "4") (pinfunction "DIN_4") (pintype "input"))
    )
    (net (code "15") (name "Net-(D101-DOUT)") (class "Default")
      (node (ref "D101") (pin "2") (pinfunction "DOUT_2") (pintype "output"))
      (node (ref "D102") (pin "4") (pinfunction "DIN_4") (pintype "input"))
    )
    (net (code "16") (name "Net-(D101-VSS)") (class "Default")
      (node (ref "C28") (pin "2") (pinfunction "2_2") (pintype "passive"))
      (node (ref "C44") (pin "2") (pinfunction "2_2") (pintype "passive"))
      (node (ref "C61") (pin "2") (pinfunction "2_2") (pintype "passive"))
      (node (ref "C78") (pin "2") (pinfunction "2_2") (pintype "passive"))
      (node (ref "C91") (pin "2") (pinfunction "2_2") (pintype "passive"))
      (node (ref "D101") (pin "3") (pinfunction "VSS_3") (pintype "passive"))
      (node (ref "D117") (pin "3") (pinfunction "VSS_3") (pintype "passive"))
      (node (ref "D134") (pin "3") (pinfunction "VSS_3") (pintype "passive"))
      (node (ref "D151") (pin "3") (pinfunction "VSS_3") (pintype "passive"))
      (node (ref "D164") (pin "3") (pinfunction "VSS_3") (pintype "passive"))
    )
    (net (code "17") (name "Net-(D102-DOUT)") (class "Default")
      (node (ref "D102") (pin "2") (pinfunction "DOUT_2") (pintype "output"))
      (node (ref "D103") (pin "4") (pinfunction "DIN_4") (pintype "input"))
    )
    (net (code "18") (name "Net-(D102-VSS)") (class "Default")
      (node (ref "C29") (pin "2") (pinfunction "2_2") (pintype "passive"))
      (node (ref "C45") (pin "2") (pinfunction "2_2") (pintype "passive"))
      (node (ref "C62") (pin "2") (pinfunction "2_2") (pintype "passive"))
      (node (ref "C79") (pin "2") (pinfunction "2_2") (pintype "passive"))
      (node (ref "C92") (pin "2") (pinfunction "2_2") (pintype "passive"))
      (node (ref "D102") (pin "3") (pinfunction "VSS_3") (pintype "passive"))
      (node (ref "D118") (pin "3") (pinfunction "VSS_3") (pintype "passive"))
      (node (ref "D135") (pin "3") (pinfunction "VSS_3") (pintype "passive"))
      (node (ref "D152") (pin "3") (pinfunction "VSS_3") (pintype "passive"))
      (node (ref "D165") (pin "3") (pinfunction "VSS_3") (pintype "passive"))
    )
    (net (code "19") (name "Net-(D103-DOUT)") (class "Default")
      (node (ref "D103") (pin "2") (pinfunction "DOUT_2") (pintype "output"))
      (node (ref "D104") (pin "4") (pinfunction "DIN_4") (pintype "input"))
    )
    (net (code "20") (name "Net-(D104-DOUT)") (class "Default")
      (node (ref "D104") (pin "2") (pinfunction "DOUT_2") (pintype "output"))
      (node (ref "D105") (pin "4") (pinfunction "DIN_4") (pintype "input"))
    )
    (net (code "21") (name "Net-(D105-DOUT)") (class "Default")
      (node (ref "D105") (pin "2") (pinfunction "DOUT_2") (pintype "output"))
      (node (ref "D106") (pin "4") (pinfunction "DIN_4") (pintype "input"))
    )
    (net (code "22") (name "Net-(D106-DOUT)") (class "Default")
      (node (ref "D106") (pin "2") (pinfunction "DOUT_2") (pintype "output"))
      (node (ref "D107") (pin "4") (pinfunction "DIN_4") (pintype "input"))
    )
    (net (code "23") (name "Net-(D107-DOUT)") (class "Default")
      (node (ref "D107") (pin "2") (pinfunction "DOUT_2") (pintype "output"))
      (node (ref "D108") (pin "4") (pinfunction "DIN_4") (pintype "input"))
    )
    (net (code "24") (name "Net-(D108-DOUT)") (class "Default")
      (node (ref "D108") (pin "2") (pinfunction "DOUT_2") (pintype "output"))
      (node (ref "D109") (pin "4") (pinfunction "DIN_4") (pintype "input"))
    )
    (net (code "25") (name "Net-(D109-DOUT)") (class "Default")
      (node (ref "D109") (pin "2") (pinfunction "DOUT_2") (pintype "output"))
      (node (ref "D110") (pin "4") (pinfunction "DIN_4") (pintype "input"))
    )
    (net (code "26") (name "Net-(D110-DOUT)") (class "Default")
      (node (ref "D110") (pin "2") (pinfunction "DOUT_2") (pintype "output"))
      (node (ref "D111") (pin "4") (pinfunction "DIN_4") (pintype "input"))
    )
    (net (code "27") (name "Net-(D111-DOUT)") (class "Default")
      (node (ref "D111") (pin "2") (pinfunction "DOUT_2") (pintype "output"))
      (node (ref "D112") (pin "4") (pinfunction "DIN_4") (pintype "input"))
    )
    (net (code "28") (name "Net-(D112-DOUT)") (class "Default")
      (node (ref "D112") (pin "2") (pinfunction "DOUT_2") (pintype "output"))
      (node (ref "D113") (pin "4") (pinfunction "DIN_4") (pintype "input"))
    )
    (net (code "29") (name "Net-(D113-DOUT)") (class "Default")
      (node (ref "D113") (pin "2") (pinfunction "DOUT_2") (pintype "output"))
      (node (ref "D114") (pin "4") (pinfunction "DIN_4") (pintype "input"))
    )
    (net (code "30") (name "Net-(D114-DOUT)") (class "Default")
      (node (ref "D114") (pin "2") (pinfunction "DOUT_2") (pintype "output"))
      (node (ref "D115") (pin "4") (pinfunction "DIN_4") (pintype "input"))
    )
    (net (code "31") (name "Net-(D115-DOUT)") (class "Default")
      (node (ref "D115") (pin "2") (pinfunction "DOUT_2") (pintype "output"))
      (node (ref "D116") (pin "4") (pinfunction "DIN_4") (pintype "input"))
    )
    (net (code "32") (name "Net-(D116-DOUT)") (class "Default")
      (node (ref "D116") (pin "2") (pinfunction "DOUT_2") (pintype "output"))
      (node (ref "D117") (pin "4") (pinfunction "DIN_4") (pintype "input"))
    )
    (net (code "33") (name "Net-(D117-DOUT)") (class "Default")
      (node (ref "D117") (pin "2") (pinfunction "DOUT_2") (pintype "output"))
      (node (ref "D118") (pin "4") (pinfunction "DIN_4") (pintype "input"))
    )
    (net (code "34") (name "Net-(D117-VDD)") (class "Default")
      (node (ref "C44") (pin "1") (pinfunction "1_1") (pintype "passive"))
      (node (ref "C61") (pin "1") (pinfunction "1_1") (pintype "passive"))
      (node (ref "C78") (pin "1") (pinfunction "1_1") (pintype "passive"))
      (node (ref "C91") (pin "1") (pinfunction "1_1") (pintype "passive"))
      (node (ref "D117") (pin "1") (pinfunction "VDD_1") (pintype "power_in"))
      (node (ref "D134") (pin "1") (pinfunction "VDD_1") (pintype "power_in"))
      (node (ref "D151") (pin "1") (pinfunction "VDD_1") (pintype "power_in"))
      (node (ref "D164") (pin "1") (pinfunction "VDD_1") (pintype "power_in"))
    )
    (net (code "35") (name "Net-(D118-DOUT)") (class "Default")
      (node (ref "D118") (pin "2") (pinfunction "DOUT_2") (pintype "output"))
      (node (ref "D119") (pin "4") (pinfunction "DIN_4") (pintype "input"))
    )
    (net (code "36") (name "Net-(D119-DOUT)") (class "Default")
      (node (ref "D119") (pin "2") (pinfunction "DOUT_2") (pintype "output"))
      (node (ref "D120") (pin "4") (pinfunction "DIN_4") (pintype "input"))
    )
    (net (code "37") (name "Net-(D120-DOUT)") (class "Default")
      (node (ref "D120") (pin "2") (pinfunction "DOUT_2") (pintype "output"))
      (node (ref "D121") (pin "4") (pinfunction "DIN_4") (pintype "input"))
    )
    (net (code "38") (name "Net-(D121-DOUT)") (class "Default")
      (node (ref "D121") (pin "2") (pinfunction "DOUT_2") (pintype "output"))
      (node (ref "D122") (pin "4") (pinfunction "DIN_4") (pintype "input"))
    )
    (net (code "39") (name "Net-(D122-DOUT)") (class "Default")
      (node (ref "D122") (pin "2") (pinfunction "DOUT_2") (pintype "output"))
      (node (ref "D123") (pin "4") (pinfunction "DIN_4") (pintype "input"))
    )
    (net (code "40") (name "Net-(D123-DOUT)") (class "Default")
      (node (ref "D123") (pin "2") (pinfunction "DOUT_2") (pintype "output"))
      (node (ref "D124") (pin "4") (pinfunction "DIN_4") (pintype "input"))
    )
    (net (code "41") (name "Net-(D124-DOUT)") (class "Default")
      (node (ref "D124") (pin "2") (pinfunction "DOUT_2") (pintype "output"))
      (node (ref "D125") (pin "4") (pinfunction "DIN_4") (pintype "input"))
    )
    (net (code "42") (name "Net-(D125-DOUT)") (class "Default")
      (node (ref "D125") (pin "2") (pinfunction "DOUT_2") (pintype "output"))
      (node (ref "D126") (pin "4") (pinfunction "DIN_4") (pintype "input"))
    )
    (net (code "43") (name "Net-(D126-DOUT)") (class "Default")
      (node (ref "D126") (pin "2") (pinfunction "DOUT_2") (pintype "output"))
      (node (ref "D127") (pin "4") (pinfunction "DIN_4") (pintype "input"))
    )
    (net (code "44") (name "Net-(D127-DOUT)") (class "Default")
      (node (ref "D127") (pin "2") (pinfunction "DOUT_2") (pintype "output"))
      (node (ref "D128") (pin "4") (pinfunction "DIN_4") (pintype "input"))
    )
    (net (code "45") (name "Net-(D128-DOUT)") (class "Default")
      (node (ref "D128") (pin "2") (pinfunction "DOUT_2") (pintype "output"))
      (node (ref "D129") (pin "4") (pinfunction "DIN_4") (pintype "input"))
    )
    (net (code "46") (name "Net-(D129-DOUT)") (class "Default")
      (node (ref "D129") (pin "2") (pinfunction "DOUT_2") (pintype "output"))
      (node (ref "D130") (pin "4") (pinfunction "DIN_4") (pintype "input"))
    )
    (net (code "47") (name "Net-(D130-DOUT)") (class "Default")
      (node (ref "D130") (pin "2") (pinfunction "DOUT_2") (pintype "output"))
      (node (ref "D131") (pin "4") (pinfunction "DIN_4") (pintype "input"))
    )
    (net (code "48") (name "Net-(D131-DOUT)") (class "Default")
      (node (ref "D131") (pin "2") (pinfunction "DOUT_2") (pintype "output"))
      (node (ref "D132") (pin "4") (pinfunction "DIN_4") (pintype "input"))
    )
    (net (code "49") (name "Net-(D132-DOUT)") (class "Default")
      (node (ref "D132") (pin "2") (pinfunction "DOUT_2") (pintype "output"))
      (node (ref "D133") (pin "4") (pinfunction "DIN_4") (pintype "input"))
    )
    (net (code "50") (name "Net-(D133-DOUT)") (class "Default")
      (node (ref "D133") (pin "2") (pinfunction "DOUT_2") (pintype "output"))
      (node (ref "D134") (pin "4") (pinfunction "DIN_4") (pintype "input"))
    )
    (net (code "51") (name "Net-(D134-DOUT)") (class "Default")
      (node (ref "D134") (pin "2") (pinfunction "DOUT_2") (pintype "output"))
      (node (ref "D135") (pin "4") (pinfunction "DIN_4") (pintype "input"))
    )
    (net (code "52") (name "Net-(D135-DOUT)") (class "Default")
      (node (ref "D135") (pin "2") (pinfunction "DOUT_2") (pintype "output"))
      (node (ref "D136") (pin "4") (pinfunction "DIN_4") (pintype "input"))
    )
    (net (code "53") (name "Net-(D136-DOUT)") (class "Default")
      (node (ref "D136") (pin "2") (pinfunction "DOUT_2") (pintype "output"))
      (node (ref "D137") (pin "4") (pinfunction "DIN_4") (pintype "input"))
    )
    (net (code "54") (name "Net-(D137-DOUT)") (class "Default")
      (node (ref "D137") (pin "2") (pinfunction "DOUT_2") (pintype "output"))
      (node (ref "D138") (pin "4") (pinfunction "DIN_4") (pintype "input"))
    )
    (net (code "55") (name "Net-(D138-DOUT)") (class "Default")
      (node (ref "D138") (pin "2") (pinfunction "DOUT_2") (pintype "output"))
      (node (ref "D139") (pin "4") (pinfunction "DIN_4") (pintype "input"))
    )
    (net (code "56") (name "Net-(D139-DOUT)") (class "Default")
      (node (ref "D139") (pin "2") (pinfunction "DOUT_2") (pintype "output"))
      (node (ref "D140") (pin "4") (pinfunction "DIN_4") (pintype "input"))
    )
    (net (code "57") (name "Net-(D140-DOUT)") (class "Default")
      (node (ref "D140") (pin "2") (pinfunction "DOUT_2") (pintype "output"))
      (node (ref "D141") (pin "4") (pinfunction "DIN_4") (pintype "input"))
    )
    (net (code "58") (name "Net-(D141-DOUT)") (class "Default")
      (node (ref "D141") (pin "2") (pinfunction "DOUT_2") (pintype "output"))
      (node (ref "D142") (pin "4") (pinfunction "DIN_4") (pintype "input"))
    )
    (net (code "59") (name "Net-(D142-DOUT)") (class "Default")
      (node (ref "D142") (pin "2") (pinfunction "DOUT_2") (pintype "output"))
      (node (ref "D143") (pin "4") (pinfunction "DIN_4") (pintype "input"))
    )
    (net (code "60") (name "Net-(D143-DOUT)") (class "Default")
      (node (ref "D143") (pin "2") (pinfunction "DOUT_2") (pintype "output"))
      (node (ref "D144") (pin "4") (pinfunction "DIN_4") (pintype "input"))
    )
    (net (code "61") (name "Net-(D144-DOUT)") (class "Default")
      (node (ref "D144") (pin "2") (pinfunction "DOUT_2") (pintype "output"))
      (node (ref "D145") (pin "4") (pinfunction "DIN_4") (pintype "input"))
    )
    (net (code "62") (name "Net-(D145-DOUT)") (class "Default")
      (node (ref "D145") (pin "2") (pinfunction "DOUT_2") (pintype "output"))
      (node (ref "D146") (pin "4") (pinfunction "DIN_4") (pintype "input"))
    )
    (net (code "63") (name "Net-(D146-DOUT)") (class "Default")
      (node (ref "D146") (pin "2") (pinfunction "DOUT_2") (pintype "output"))
      (node (ref "D147") (pin "4") (pinfunction "DIN_4") (pintype "input"))
    )
    (net (code "64") (name "Net-(D147-DOUT)") (class "Default")
      (node (ref "D147") (pin "2") (pinfunction "DOUT_2") (pintype "output"))
      (node (ref "D148") (pin "4") (pinfunction "DIN_4") (pintype "input"))
    )
    (net (code "65") (name "Net-(D148-DOUT)") (class "Default")
      (node (ref "D148") (pin "2") (pinfunction "DOUT_2") (pintype "output"))
      (node (ref "D149") (pin "4") (pinfunction "DIN_4") (pintype "input"))
    )
    (net (code "66") (name "Net-(D149-DOUT)") (class "Default")
      (node (ref "D149") (pin "2") (pinfunction "DOUT_2") (pintype "output"))
      (node (ref "D150") (pin "4") (pinfunction "DIN_4") (pintype "input"))
    )
    (net (code "67") (name "Net-(D150-DOUT)") (class "Default")
      (node (ref "D150") (pin "2") (pinfunction "DOUT_2") (pintype "output"))
      (node (ref "D151") (pin "4") (pinfunction "DIN_4") (pintype "input"))
    )
    (net (code "68") (name "Net-(D151-DOUT)") (class "Default")
      (node (ref "D151") (pin "2") (pinfunction "DOUT_2") (pintype "output"))
      (node (ref "D152") (pin "4") (pinfunction "DIN_4") (pintype "input"))
    )
    (net (code "69") (name "Net-(D152-DOUT)") (class "Default")
      (node (ref "D152") (pin "2") (pinfunction "DOUT_2") (pintype "output"))
      (node (ref "D153") (pin "4") (pinfunction "DIN_4") (pintype "input"))
    )
    (net (code "70") (name "Net-(D153-DOUT)") (class "Default")
      (node (ref "D153") (pin "2") (pinfunction "DOUT_2") (pintype "output"))
      (node (ref "D154") (pin "4") (pinfunction "DIN_4") (pintype "input"))
    )
    (net (code "71") (name "Net-(D154-DOUT)") (class "Default")
      (node (ref "D154") (pin "2") (pinfunction "DOUT_2") (pintype "output"))
      (node (ref "D155") (pin "4") (pinfunction "DIN_4") (pintype "input"))
    )
    (net (code "72") (name "Net-(D155-DOUT)") (class "Default")
      (node (ref "D155") (pin "2") (pinfunction "DOUT_2") (pintype "output"))
      (node (ref "D156") (pin "4") (pinfunction "DIN_4") (pintype "input"))
    )
    (net (code "73") (name "Net-(D156-DOUT)") (class "Default")
      (node (ref "D156") (pin "2") (pinfunction "DOUT_2") (pintype "output"))
      (node (ref "D157") (pin "4") (pinfunction "DIN_4") (pintype "input"))
    )
    (net (code "74") (name "Net-(D157-DOUT)") (class "Default")
      (node (ref "D157") (pin "2") (pinfunction "DOUT_2") (pintype "output"))
      (node (ref "D158") (pin "4") (pinfunction "DIN_4") (pintype "input"))
    )
    (net (code "75") (name "Net-(D158-DOUT)") (class "Default")
      (node (ref "D158") (pin "2") (pinfunction "DOUT_2") (pintype "output"))
      (node (ref "D159") (pin "4") (pinfunction "DIN_4") (pintype "input"))
    )
    (net (code "76") (name "Net-(D159-DOUT)") (class "Default")
      (node (ref "D159") (pin "2") (pinfunction "DOUT_2") (pintype "output"))
      (node (ref "D160") (pin "4") (pinfunction "DIN_4") (pintype "input"))
    )
    (net (code "77") (name "Net-(D160-DOUT)") (class "Default")
      (node (ref "D160") (pin "2") (pinfunction "DOUT_2") (pintype "output"))
      (node (ref "D161") (pin "4") (pinfunction "DIN_4") (pintype "input"))
    )
    (net (code "78") (name "Net-(D161-DOUT)") (class "Default")
      (node (ref "D161") (pin "2") (pinfunction "DOUT_2") (pintype "output"))
      (node (ref "D162") (pin "4") (pinfunction "DIN_4") (pintype "input"))
    )
    (net (code "79") (name "Net-(D162-DOUT)") (class "Default")
      (node (ref "D162") (pin "2") (pinfunction "DOUT_2") (pintype "output"))
      (node (ref "D163") (pin "4") (pinfunction "DIN_4") (pintype "input"))
    )
    (net (code "80") (name "Net-(D163-DOUT)") (class "Default")
      (node (ref "D163") (pin "2") (pinfunction "DOUT_2") (pintype "output"))
      (node (ref "D164") (pin "4") (pinfunction "DIN_4") (pintype "input"))
    )
    (net (code "81") (name "Net-(D164-DOUT)") (class "Default")
      (node (ref "D164") (pin "2") (pinfunction "DOUT_2") (pintype "output"))
      (node (ref "D165") (pin "4") (pinfunction "DIN_4") (pintype "input"))
    )
    (net (code "82") (name "Net-(D165-DOUT)") (class "Default")
      (node (ref "D165") (pin "2") (pinfunction "DOUT_2") (pintype "output"))
      (node (ref "D166") (pin "4") (pinfunction "DIN_4") (pintype "input"))
    )
    (net (code "83") (name "Net-(D166-DOUT)") (class "Default")
      (node (ref "D166") (pin "2") (pinfunction "DOUT_2") (pintype "output"))
      (node (ref "D167") (pin "4") (pinfunction "DIN_4") (pintype "input"))
    )
    (net (code "84") (name "Net-(D167-DOUT)") (class "Default")
      (node (ref "D167") (pin "2") (pinfunction "DOUT_2") (pintype "output"))
      (node (ref "D168") (pin "4") (pinfunction "DIN_4") (pintype "input"))
    )
    (net (code "85") (name "Net-(D168-DOUT)") (class "Default")
      (node (ref "D168") (pin "2") (pinfunction "DOUT_2") (pintype "output"))
      (node (ref "D169") (pin "4") (pinfunction "DIN_4") (pintype "input"))
    )
    (net (code "86") (name "Net-(D169-DOUT)") (class "Default")
      (node (ref "D169") (pin "2") (pinfunction "DOUT_2") (pintype "output"))
      (node (ref "D170") (pin "4") (pinfunction "DIN_4") (pintype "input"))
    )
    (net (code "87") (name "Net-(D170-DOUT)") (class "Default")
      (node (ref "D170") (pin "2") (pinfunction "DOUT_2") (pintype "output"))
      (node (ref "D171") (pin "4") (pinfunction "DIN_4") (pintype "input"))
    )
    (net (code "88") (name "Net-(D171-DOUT)") (class "Default")
      (node (ref "D171") (pin "2") (pinfunction "DOUT_2") (pintype "output"))
      (node (ref "D172") (pin "4") (pinfunction "DIN_4") (pintype "input"))
    )
    (net (code "89") (name "Net-(D172-DOUT)") (class "Default")
      (node (ref "D172") (pin "2") (pinfunction "DOUT_2") (pintype "output"))
      (node (ref "D173") (pin "4") (pinfunction "DIN_4") (pintype "input"))
    )
    (net (code "90") (name "RGB") (class "Default")
      (node (ref "U12") (pin "2") (pinfunction "A_2") (pintype "input"))
    )
    (net (code "91") (name "unconnected-(C77-Pad2)") (class "Default")
      (node (ref "C77") (pin "2") (pinfunction "2_2") (pintype "passive"))
    )
    (net (code "92") (name "unconnected-(D173-DOUT-Pad2)") (class "Default")
      (node (ref "D173") (pin "2") (pinfunction "DOUT_2") (pintype "output"))
    )
  )
)
